# sboardnew.net
KiCad netlist of a schematic drawn in EAGLE
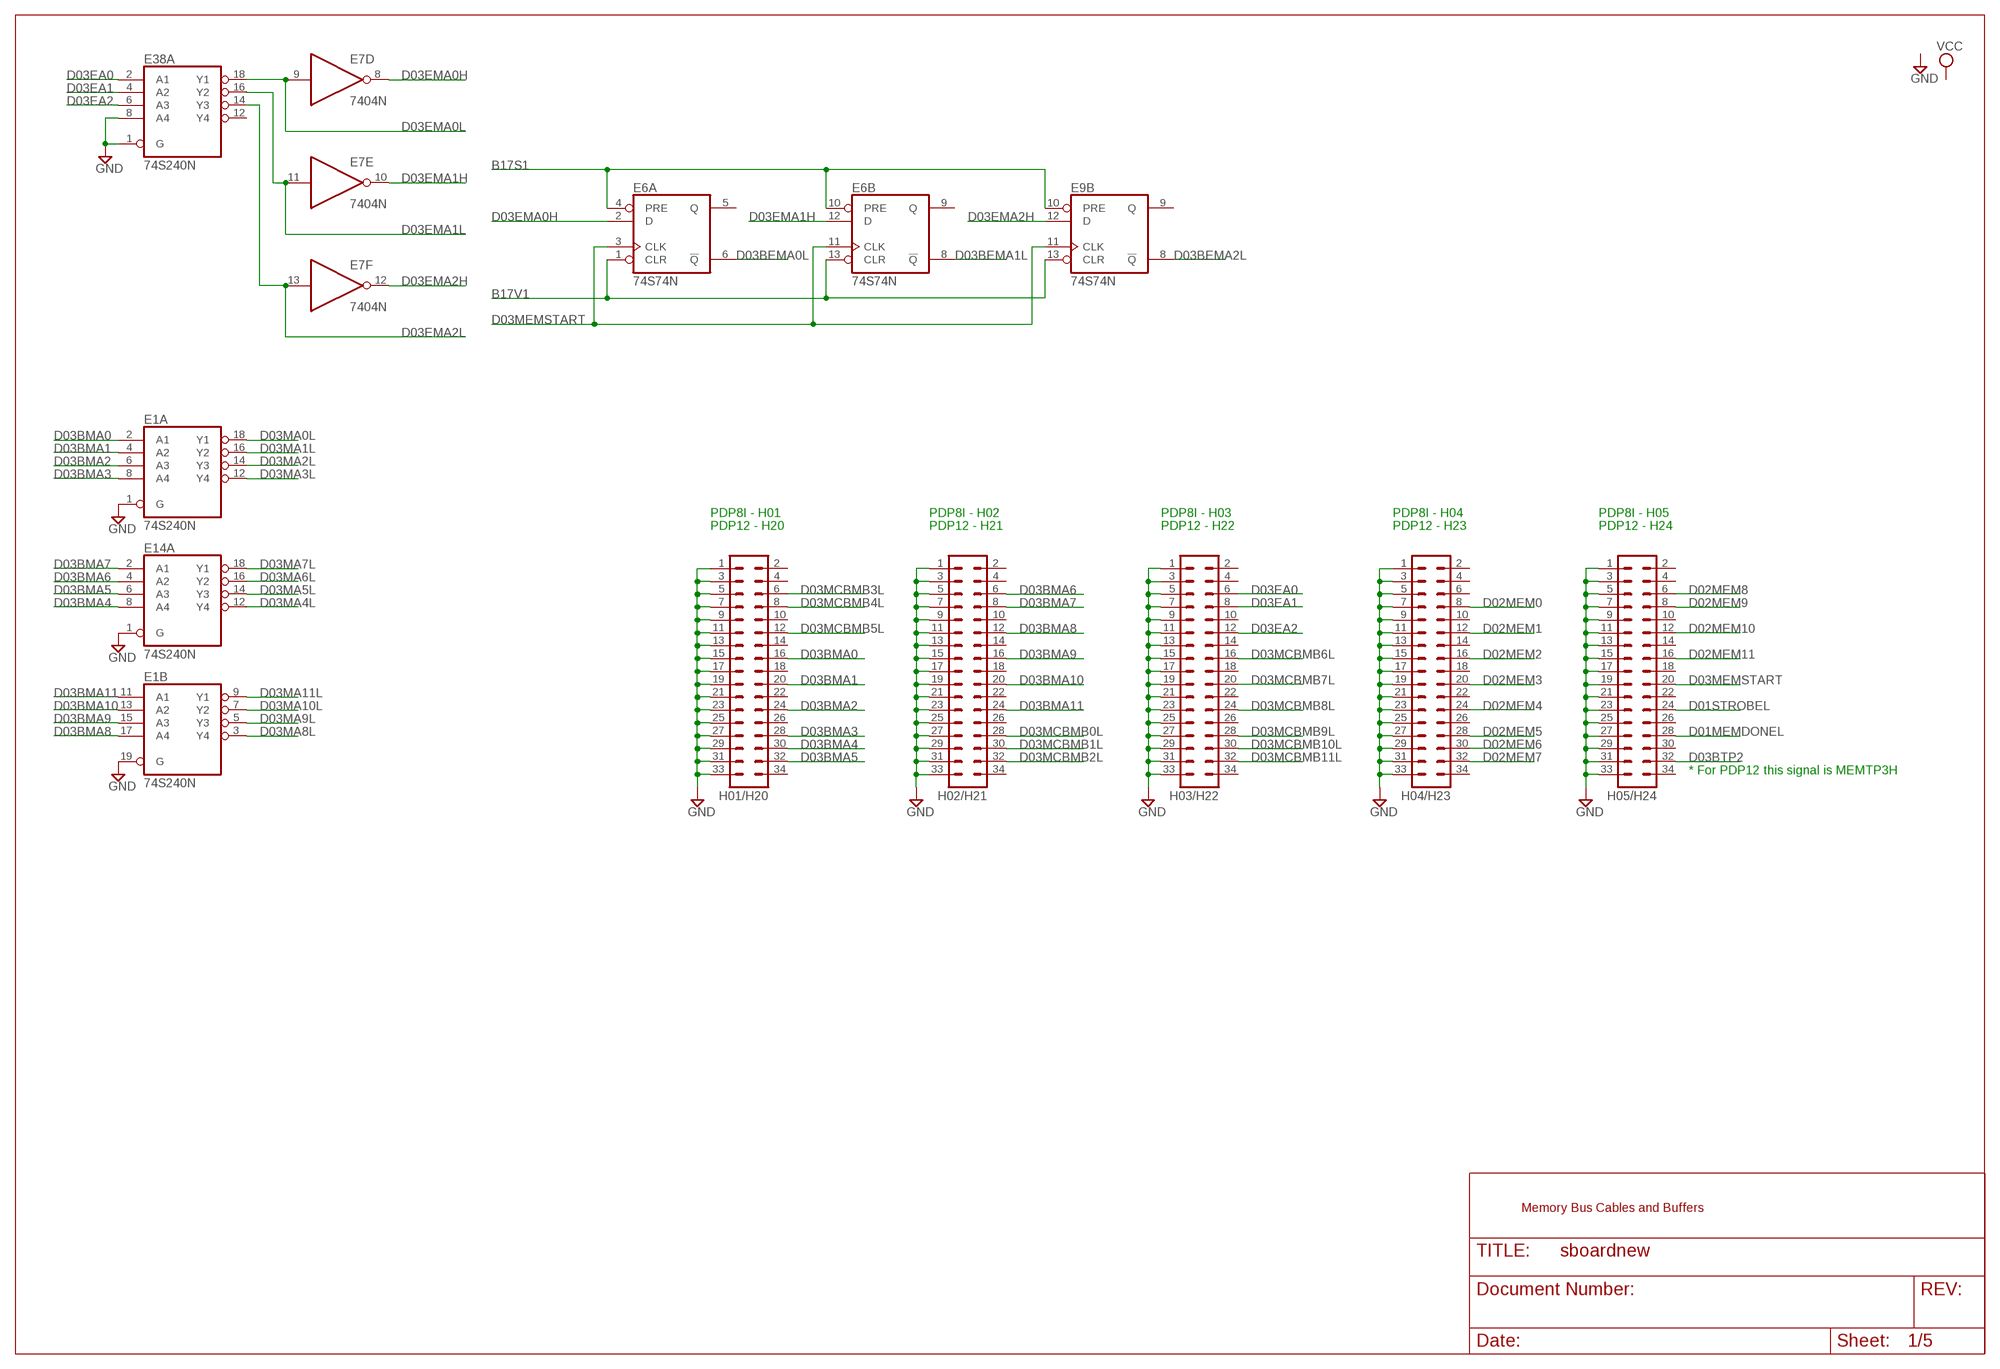
[diagram p0: schematic, sheet 1]
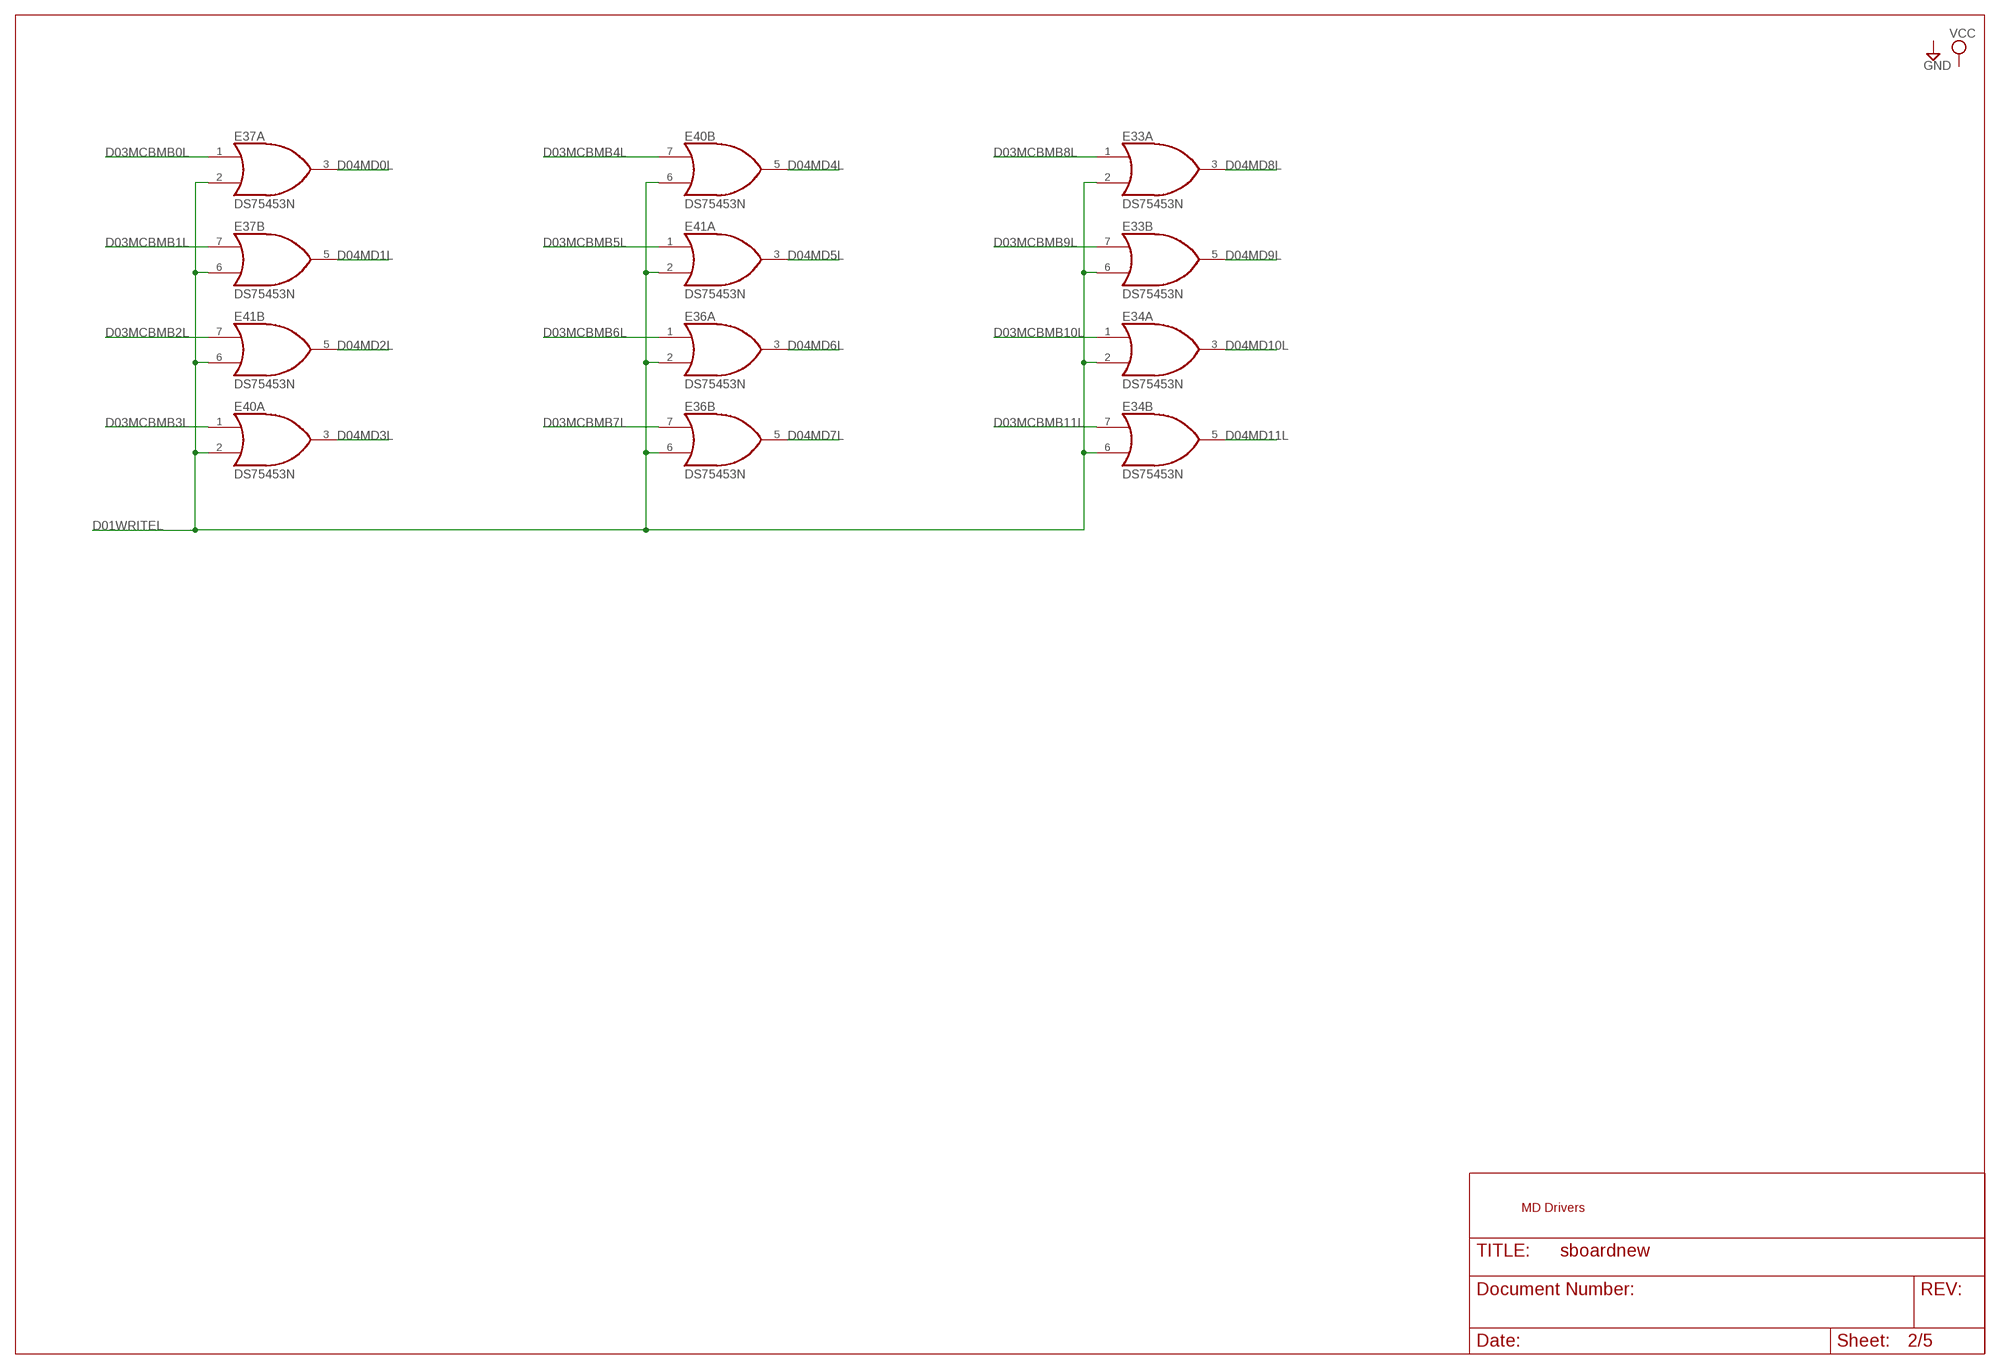
[diagram p1: schematic, sheet 2]
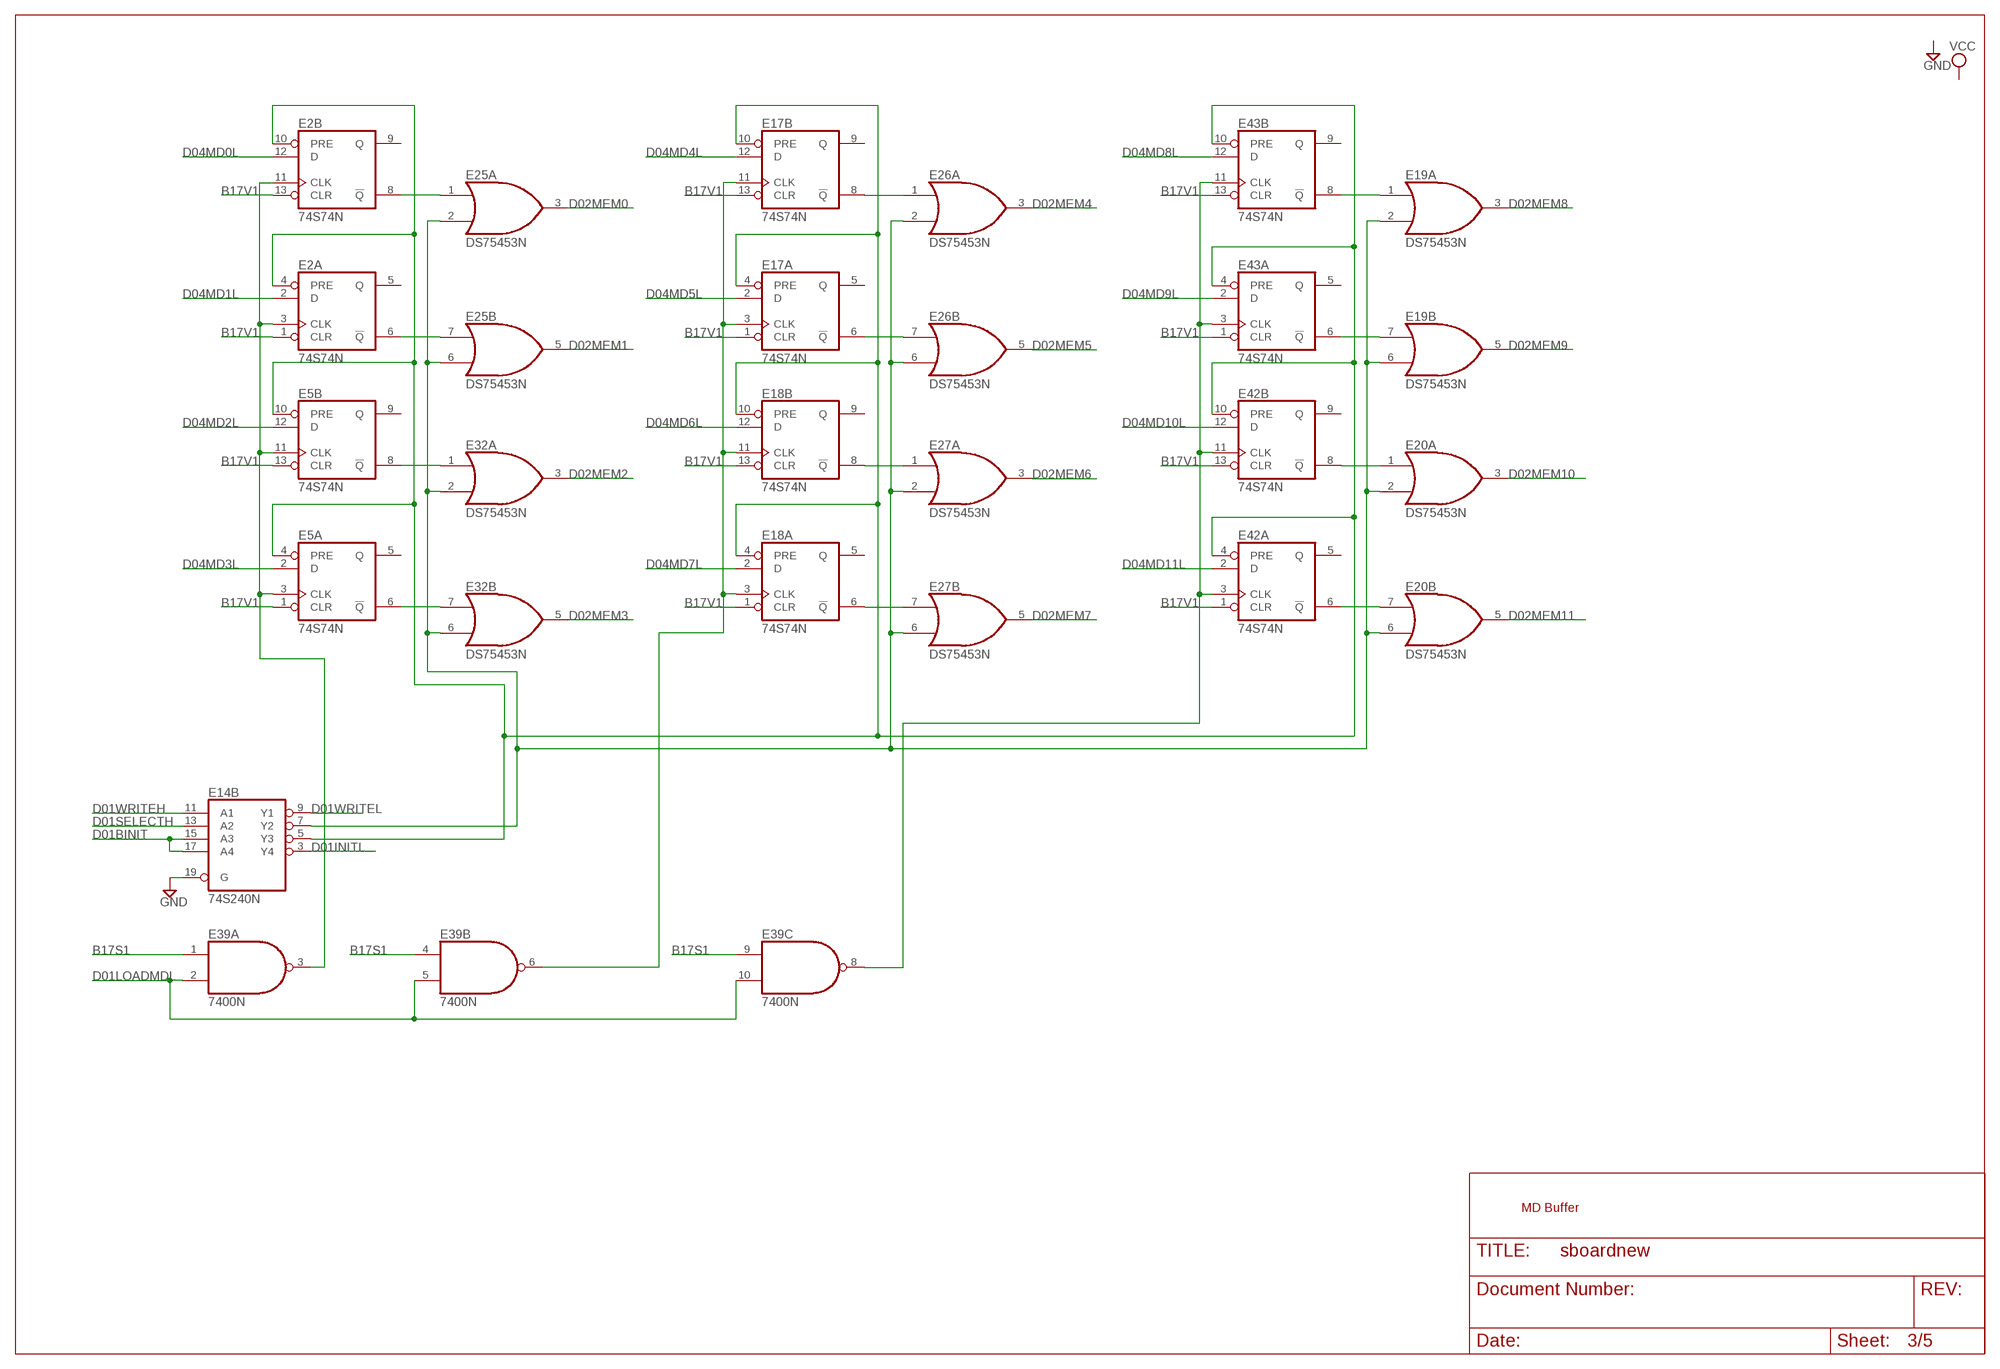
[diagram p2: schematic, sheet 3]
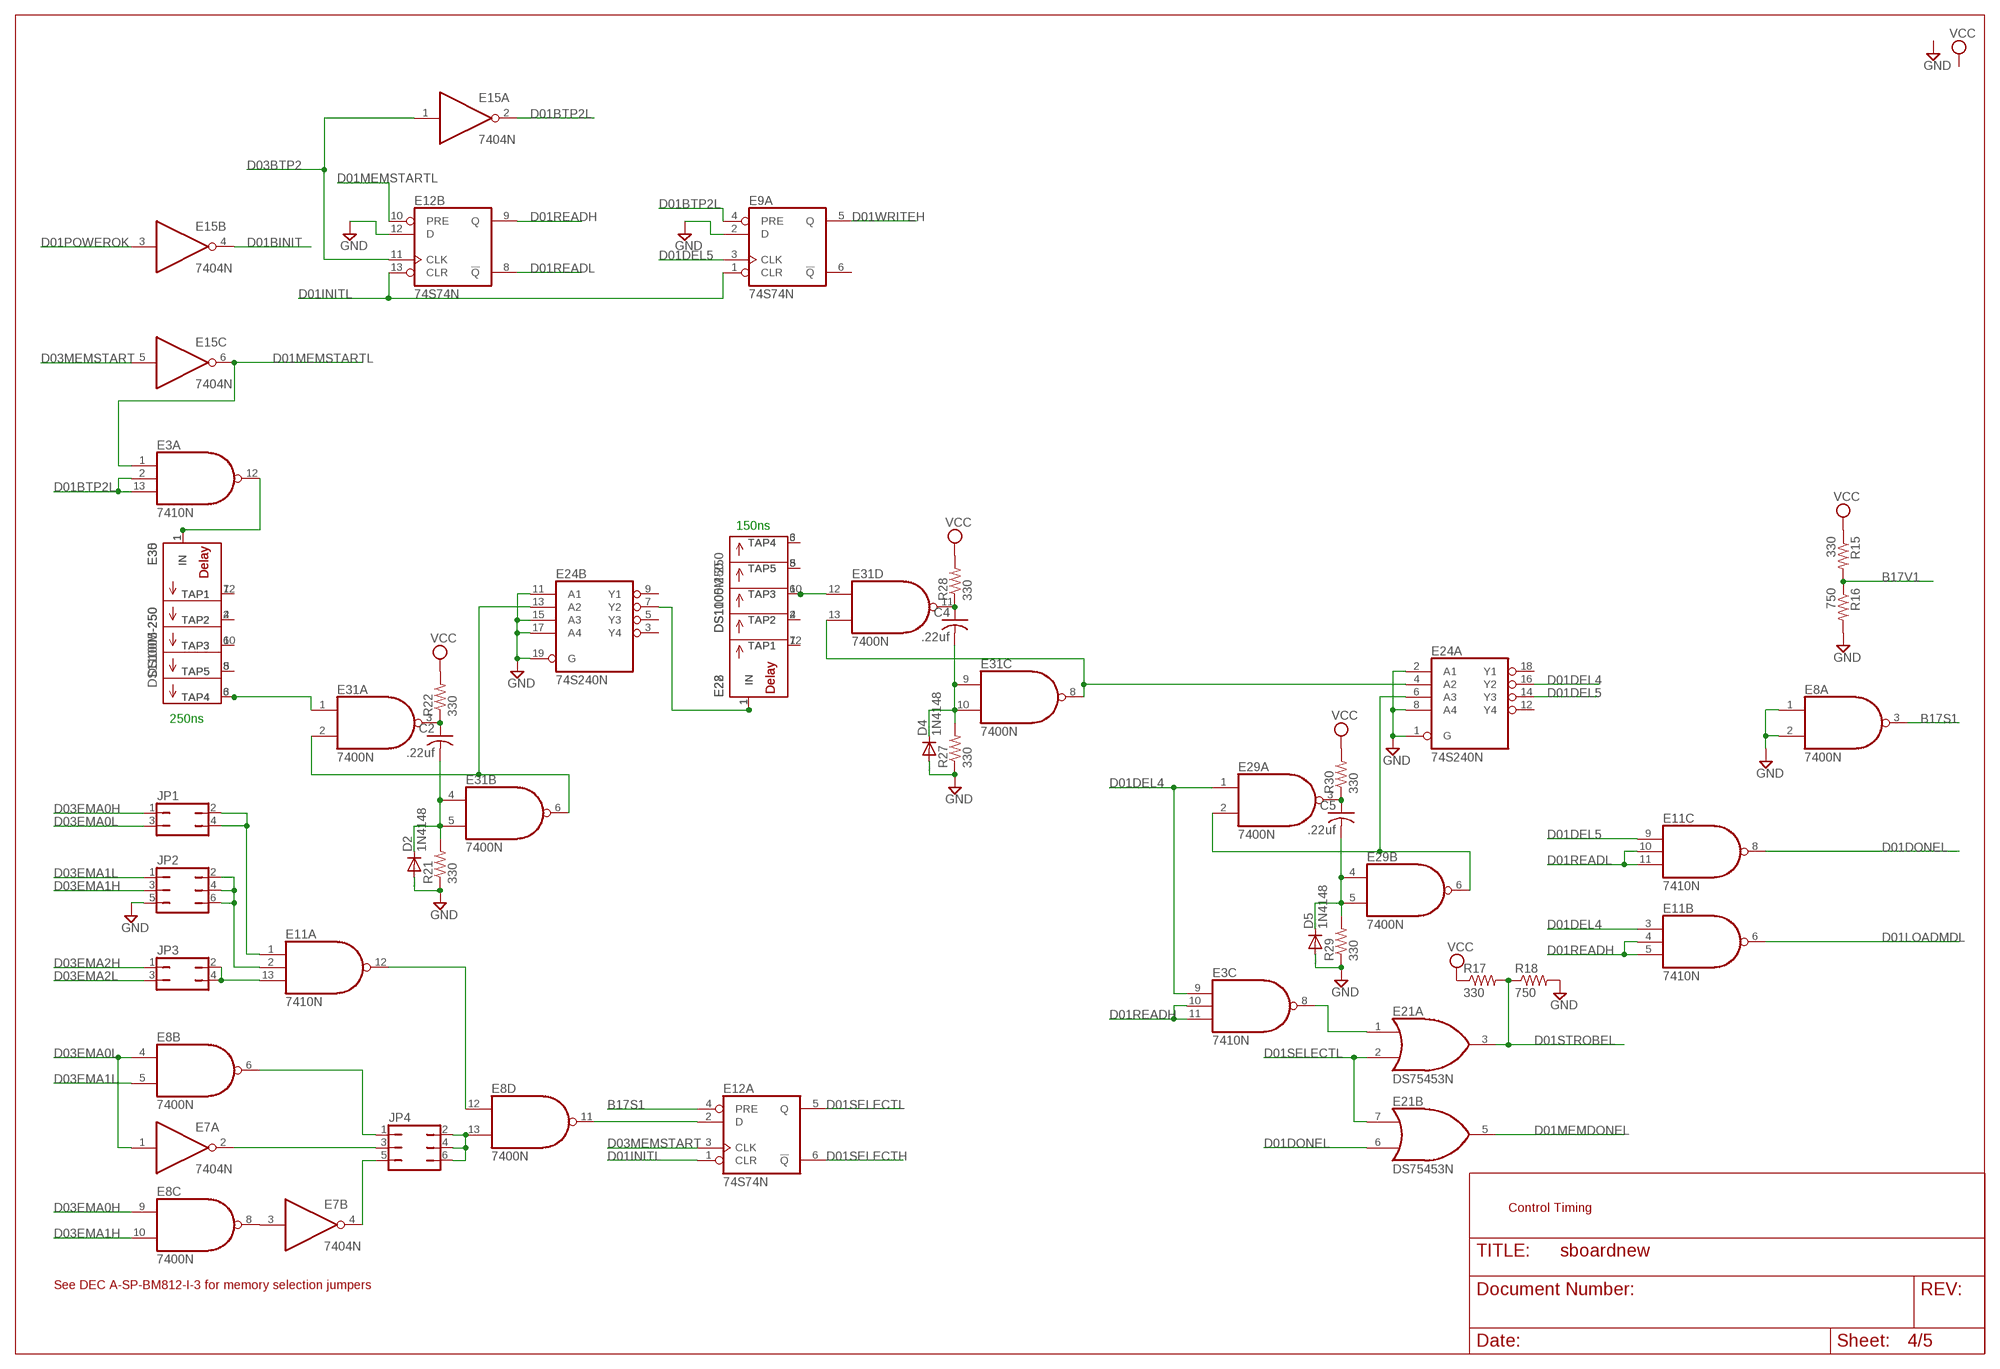
[diagram p3: schematic, sheet 4]
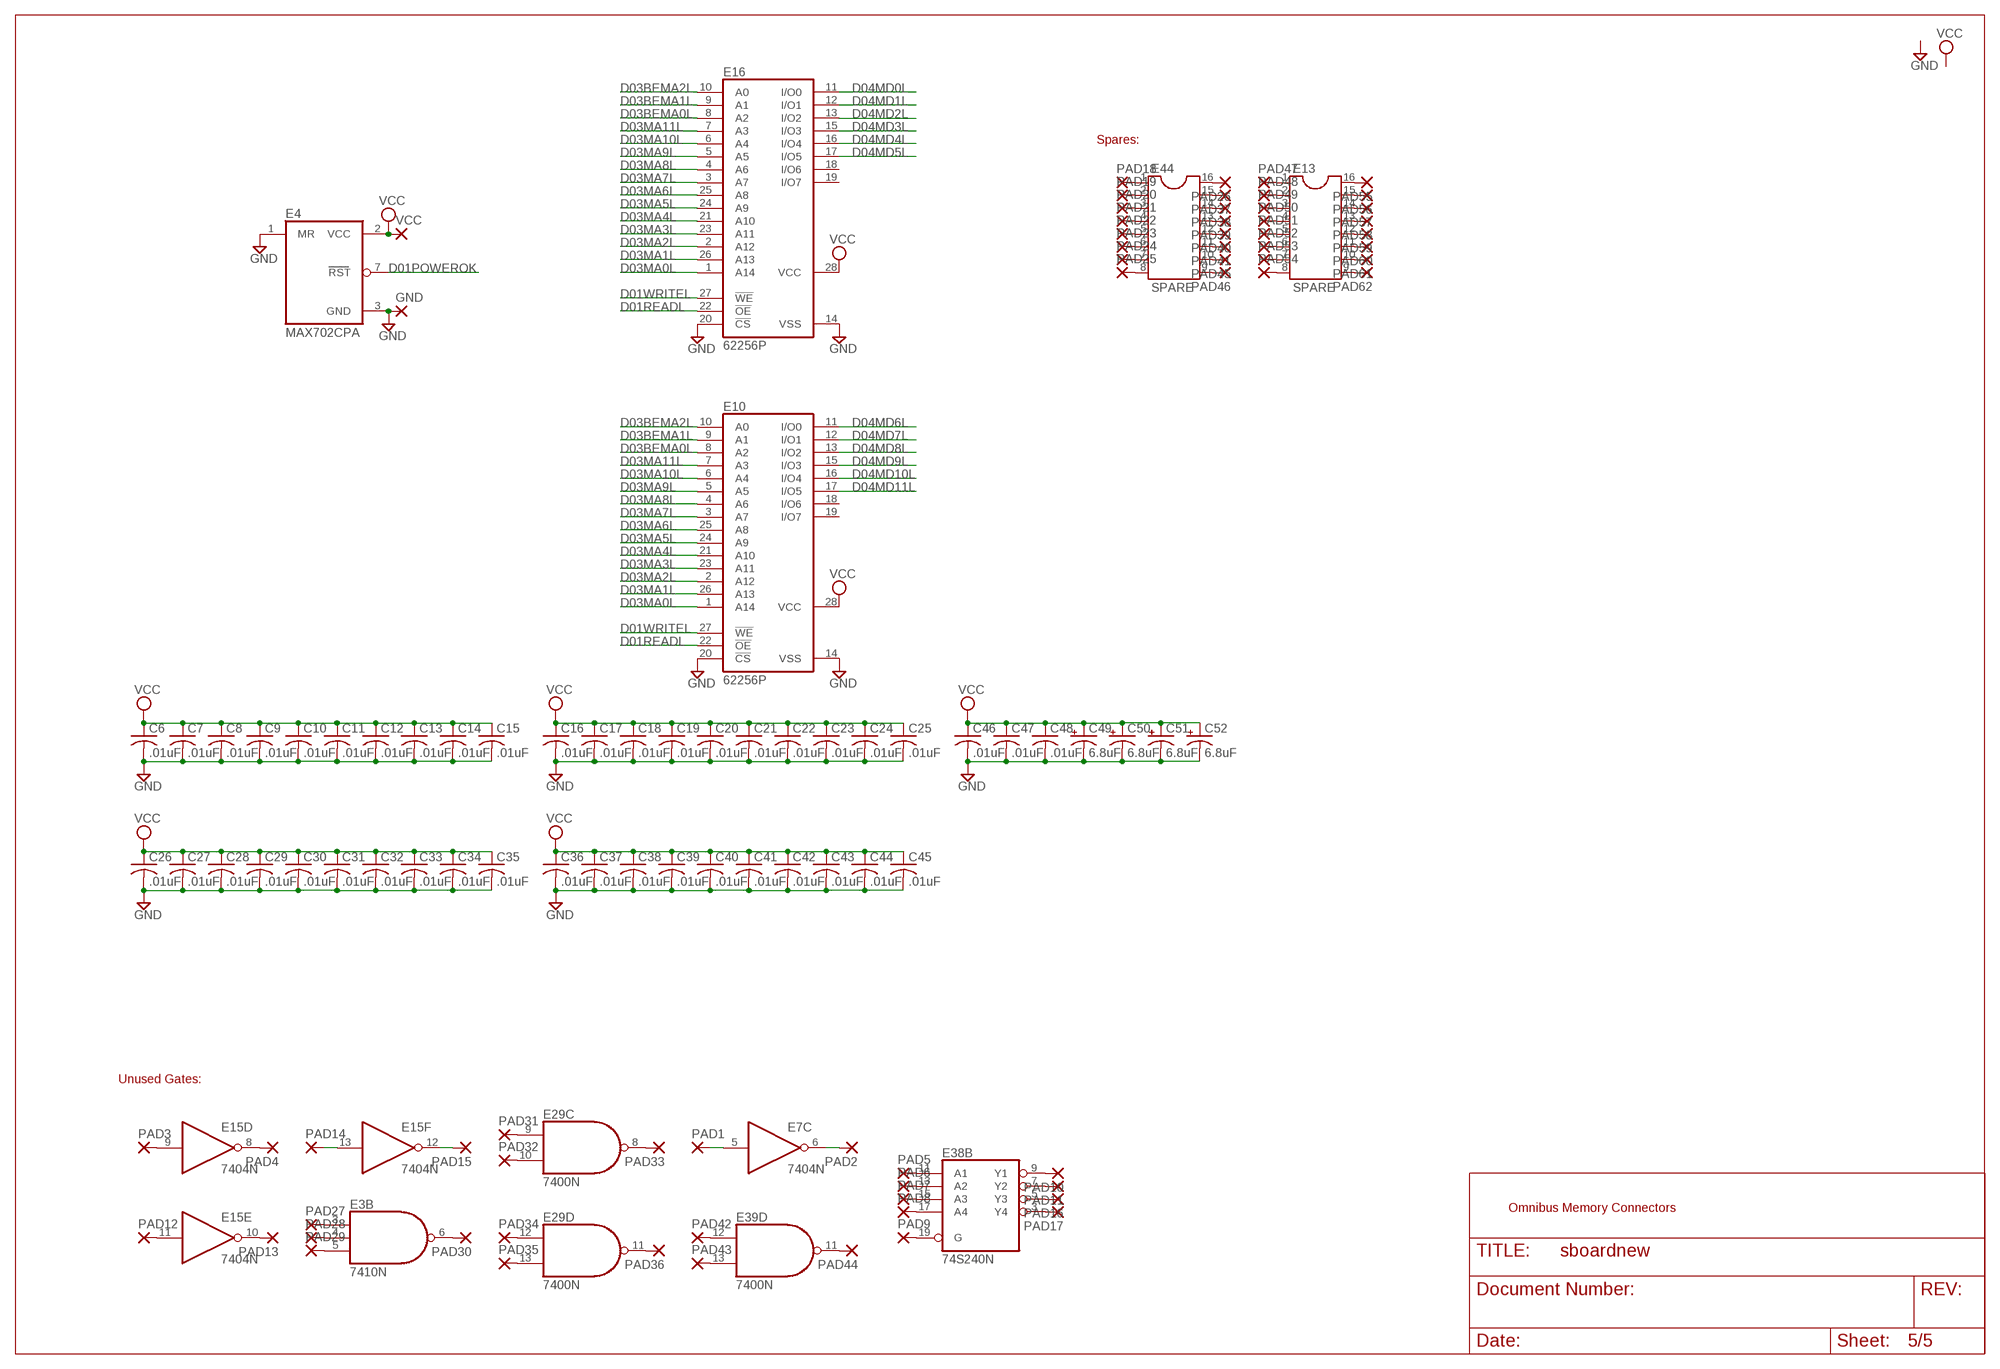
[diagram p4: schematic, sheet 5]

(export (version "E")
  (design (tool "Eeschema 10.0.6"))
  (components
    (comp (ref "E2")
      (value "74S74N")
      (footprint "eagle-import:DIL14")
      (libsource (lib "eagle-import") (part "7474NS"))
    )
    (comp (ref "E5")
      (value "74S74N")
      (footprint "eagle-import:DIL14")
      (libsource (lib "eagle-import") (part "7474NS"))
    )
    (comp (ref "E14")
      (value "74S240N")
      (footprint "eagle-import:DIL20")
      (libsource (lib "eagle-import") (part "74240NS"))
    )
    (comp (ref "E17")
      (value "74S74N")
      (footprint "eagle-import:DIL14")
      (libsource (lib "eagle-import") (part "7474NS"))
    )
    (comp (ref "E18")
      (value "74S74N")
      (footprint "eagle-import:DIL14")
      (libsource (lib "eagle-import") (part "7474NS"))
    )
    (comp (ref "E19")
      (value "DS75453N")
      (footprint "eagle-import:DIL08")
      (libsource (lib "eagle-import") (part "DS75453N"))
    )
    (comp (ref "E20")
      (value "DS75453N")
      (footprint "eagle-import:DIL08")
      (libsource (lib "eagle-import") (part "DS75453N"))
    )
    (comp (ref "E25")
      (value "DS75453N")
      (footprint "eagle-import:DIL08")
      (libsource (lib "eagle-import") (part "DS75453N"))
    )
    (comp (ref "E26")
      (value "DS75453N")
      (footprint "eagle-import:DIL08")
      (libsource (lib "eagle-import") (part "DS75453N"))
    )
    (comp (ref "E27")
      (value "DS75453N")
      (footprint "eagle-import:DIL08")
      (libsource (lib "eagle-import") (part "DS75453N"))
    )
    (comp (ref "E32")
      (value "DS75453N")
      (footprint "eagle-import:DIL08")
      (libsource (lib "eagle-import") (part "DS75453N"))
    )
    (comp (ref "E39")
      (value "7400N")
      (footprint "eagle-import:DIL14")
      (libsource (lib "eagle-import") (part "7400N"))
    )
    (comp (ref "E42")
      (value "74S74N")
      (footprint "eagle-import:DIL14")
      (libsource (lib "eagle-import") (part "7474NS"))
    )
    (comp (ref "E43")
      (value "74S74N")
      (footprint "eagle-import:DIL14")
      (libsource (lib "eagle-import") (part "7474NS"))
    )
    (comp (ref "C6")
      (value ".01uF")
      (footprint "eagle-import:C050-025X075")
      (libsource (lib "eagle-import") (part "C-US050-025X075"))
    )
    (comp (ref "C7")
      (value ".01uF")
      (footprint "eagle-import:C050-025X075")
      (libsource (lib "eagle-import") (part "C-US050-025X075"))
    )
    (comp (ref "C8")
      (value ".01uF")
      (footprint "eagle-import:C050-025X075")
      (libsource (lib "eagle-import") (part "C-US050-025X075"))
    )
    (comp (ref "C9")
      (value ".01uF")
      (footprint "eagle-import:C050-025X075")
      (libsource (lib "eagle-import") (part "C-US050-025X075"))
    )
    (comp (ref "C10")
      (value ".01uF")
      (footprint "eagle-import:C050-025X075")
      (libsource (lib "eagle-import") (part "C-US050-025X075"))
    )
    (comp (ref "C11")
      (value ".01uF")
      (footprint "eagle-import:C050-025X075")
      (libsource (lib "eagle-import") (part "C-US050-025X075"))
    )
    (comp (ref "C12")
      (value ".01uF")
      (footprint "eagle-import:C050-025X075")
      (libsource (lib "eagle-import") (part "C-US050-025X075"))
    )
    (comp (ref "C13")
      (value ".01uF")
      (footprint "eagle-import:C050-025X075")
      (libsource (lib "eagle-import") (part "C-US050-025X075"))
    )
    (comp (ref "C14")
      (value ".01uF")
      (footprint "eagle-import:C050-025X075")
      (libsource (lib "eagle-import") (part "C-US050-025X075"))
    )
    (comp (ref "C15")
      (value ".01uF")
      (footprint "eagle-import:C050-025X075")
      (libsource (lib "eagle-import") (part "C-US050-025X075"))
    )
    (comp (ref "C16")
      (value ".01uF")
      (footprint "eagle-import:C050-025X075")
      (libsource (lib "eagle-import") (part "C-US050-025X075"))
    )
    (comp (ref "C17")
      (value ".01uF")
      (footprint "eagle-import:C050-025X075")
      (libsource (lib "eagle-import") (part "C-US050-025X075"))
    )
    (comp (ref "C18")
      (value ".01uF")
      (footprint "eagle-import:C050-025X075")
      (libsource (lib "eagle-import") (part "C-US050-025X075"))
    )
    (comp (ref "C19")
      (value ".01uF")
      (footprint "eagle-import:C050-025X075")
      (libsource (lib "eagle-import") (part "C-US050-025X075"))
    )
    (comp (ref "C20")
      (value ".01uF")
      (footprint "eagle-import:C050-025X075")
      (libsource (lib "eagle-import") (part "C-US050-025X075"))
    )
    (comp (ref "C21")
      (value ".01uF")
      (footprint "eagle-import:C050-025X075")
      (libsource (lib "eagle-import") (part "C-US050-025X075"))
    )
    (comp (ref "C22")
      (value ".01uF")
      (footprint "eagle-import:C050-025X075")
      (libsource (lib "eagle-import") (part "C-US050-025X075"))
    )
    (comp (ref "C23")
      (value ".01uF")
      (footprint "eagle-import:C050-025X075")
      (libsource (lib "eagle-import") (part "C-US050-025X075"))
    )
    (comp (ref "C24")
      (value ".01uF")
      (footprint "eagle-import:C050-025X075")
      (libsource (lib "eagle-import") (part "C-US050-025X075"))
    )
    (comp (ref "C25")
      (value ".01uF")
      (footprint "eagle-import:C050-025X075")
      (libsource (lib "eagle-import") (part "C-US050-025X075"))
    )
    (comp (ref "C26")
      (value ".01uF")
      (footprint "eagle-import:C050-025X075")
      (libsource (lib "eagle-import") (part "C-US050-025X075"))
    )
    (comp (ref "C27")
      (value ".01uF")
      (footprint "eagle-import:C050-025X075")
      (libsource (lib "eagle-import") (part "C-US050-025X075"))
    )
    (comp (ref "C28")
      (value ".01uF")
      (footprint "eagle-import:C050-025X075")
      (libsource (lib "eagle-import") (part "C-US050-025X075"))
    )
    (comp (ref "C29")
      (value ".01uF")
      (footprint "eagle-import:C050-025X075")
      (libsource (lib "eagle-import") (part "C-US050-025X075"))
    )
    (comp (ref "C30")
      (value ".01uF")
      (footprint "eagle-import:C050-025X075")
      (libsource (lib "eagle-import") (part "C-US050-025X075"))
    )
    (comp (ref "C31")
      (value ".01uF")
      (footprint "eagle-import:C050-025X075")
      (libsource (lib "eagle-import") (part "C-US050-025X075"))
    )
    (comp (ref "C32")
      (value ".01uF")
      (footprint "eagle-import:C050-025X075")
      (libsource (lib "eagle-import") (part "C-US050-025X075"))
    )
    (comp (ref "C33")
      (value ".01uF")
      (footprint "eagle-import:C050-025X075")
      (libsource (lib "eagle-import") (part "C-US050-025X075"))
    )
    (comp (ref "C34")
      (value ".01uF")
      (footprint "eagle-import:C050-025X075")
      (libsource (lib "eagle-import") (part "C-US050-025X075"))
    )
    (comp (ref "C35")
      (value ".01uF")
      (footprint "eagle-import:C050-025X075")
      (libsource (lib "eagle-import") (part "C-US050-025X075"))
    )
    (comp (ref "C36")
      (value ".01uF")
      (footprint "eagle-import:C050-025X075")
      (libsource (lib "eagle-import") (part "C-US050-025X075"))
    )
    (comp (ref "C37")
      (value ".01uF")
      (footprint "eagle-import:C050-025X075")
      (libsource (lib "eagle-import") (part "C-US050-025X075"))
    )
    (comp (ref "C38")
      (value ".01uF")
      (footprint "eagle-import:C050-025X075")
      (libsource (lib "eagle-import") (part "C-US050-025X075"))
    )
    (comp (ref "C39")
      (value ".01uF")
      (footprint "eagle-import:C050-025X075")
      (libsource (lib "eagle-import") (part "C-US050-025X075"))
    )
    (comp (ref "C40")
      (value ".01uF")
      (footprint "eagle-import:C050-025X075")
      (libsource (lib "eagle-import") (part "C-US050-025X075"))
    )
    (comp (ref "C41")
      (value ".01uF")
      (footprint "eagle-import:C050-025X075")
      (libsource (lib "eagle-import") (part "C-US050-025X075"))
    )
    (comp (ref "C42")
      (value ".01uF")
      (footprint "eagle-import:C050-025X075")
      (libsource (lib "eagle-import") (part "C-US050-025X075"))
    )
    (comp (ref "C43")
      (value ".01uF")
      (footprint "eagle-import:C050-025X075")
      (libsource (lib "eagle-import") (part "C-US050-025X075"))
    )
    (comp (ref "C44")
      (value ".01uF")
      (footprint "eagle-import:C050-025X075")
      (libsource (lib "eagle-import") (part "C-US050-025X075"))
    )
    (comp (ref "C45")
      (value ".01uF")
      (footprint "eagle-import:C050-025X075")
      (libsource (lib "eagle-import") (part "C-US050-025X075"))
    )
    (comp (ref "C46")
      (value ".01uF")
      (footprint "eagle-import:C050-025X075")
      (libsource (lib "eagle-import") (part "C-US050-025X075"))
    )
    (comp (ref "C47")
      (value ".01uF")
      (footprint "eagle-import:C050-025X075")
      (libsource (lib "eagle-import") (part "C-US050-025X075"))
    )
    (comp (ref "C48")
      (value ".01uF")
      (footprint "eagle-import:C050-025X075")
      (libsource (lib "eagle-import") (part "C-US050-025X075"))
    )
    (comp (ref "C49")
      (value "6.8uF")
      (footprint "eagle-import:E22-6")
      (libsource (lib "eagle-import") (part "CPOL-USE22-6AXIAL"))
    )
    (comp (ref "C50")
      (value "6.8uF")
      (footprint "eagle-import:E22-6")
      (libsource (lib "eagle-import") (part "CPOL-USE22-6AXIAL"))
    )
    (comp (ref "C51")
      (value "6.8uF")
      (footprint "eagle-import:E22-6")
      (libsource (lib "eagle-import") (part "CPOL-USE22-6AXIAL"))
    )
    (comp (ref "C52")
      (value "6.8uF")
      (footprint "eagle-import:E22-6")
      (libsource (lib "eagle-import") (part "CPOL-USE22-6AXIAL"))
    )
    (comp (ref "E3")
      (value "7410N")
      (footprint "eagle-import:DIL14")
      (libsource (lib "eagle-import") (part "7410N"))
    )
    (comp (ref "E4")
      (value "MAX702CPA")
      (footprint "eagle-import:DIL08")
      (fields (field (name "MF") "MAXIM") (field (name "MPN") "MAX702CPA+"))
      (libsource (lib "eagle-import") (part "MAX702CPA"))
    )
    (comp (ref "E7")
      (value "7404N")
      (footprint "eagle-import:DIL14")
      (libsource (lib "eagle-import") (part "7404N"))
    )
    (comp (ref "E10")
      (value "62256P")
      (footprint "eagle-import:DIL28-6")
      (libsource (lib "eagle-import") (part "62256P"))
    )
    (comp (ref "E13")
      (value "SPARE")
      (footprint "eagle-import:DIL16")
      (libsource (lib "eagle-import") (part "DIL16"))
    )
    (comp (ref "E15")
      (value "7404N")
      (footprint "eagle-import:DIL14")
      (libsource (lib "eagle-import") (part "7404N"))
    )
    (comp (ref "E16")
      (value "62256P")
      (footprint "eagle-import:DIL28-6")
      (libsource (lib "eagle-import") (part "62256P"))
    )
    (comp (ref "E29")
      (value "7400N")
      (footprint "eagle-import:DIL14")
      (libsource (lib "eagle-import") (part "7400N"))
    )
    (comp (ref "E38")
      (value "74S240N")
      (footprint "eagle-import:DIL20")
      (libsource (lib "eagle-import") (part "74240NS"))
    )
    (comp (ref "E44")
      (value "SPARE")
      (footprint "eagle-import:DIL16")
      (libsource (lib "eagle-import") (part "DIL16"))
    )
    (comp (ref "GND")
      (value "2,15/1,0")
      (footprint "eagle-import:2,15_1,0")
      (libsource (lib "eagle-import") (part "2,15/1,0"))
    )
    (comp (ref "PAD1")
      (value "1,6/0,8")
      (footprint "eagle-import:1,6_0,8")
      (libsource (lib "eagle-import") (part "1,6/0,8"))
    )
    (comp (ref "PAD2")
      (value "1,6/0,8")
      (footprint "eagle-import:1,6_0,8")
      (libsource (lib "eagle-import") (part "1,6/0,8"))
    )
    (comp (ref "PAD3")
      (value "1,6/0,8")
      (footprint "eagle-import:1,6_0,8")
      (libsource (lib "eagle-import") (part "1,6/0,8"))
    )
    (comp (ref "PAD4")
      (value "1,6/0,8")
      (footprint "eagle-import:1,6_0,8")
      (libsource (lib "eagle-import") (part "1,6/0,8"))
    )
    (comp (ref "PAD5")
      (value "1,6/0,8")
      (footprint "eagle-import:1,6_0,8")
      (libsource (lib "eagle-import") (part "1,6/0,8"))
    )
    (comp (ref "PAD6")
      (value "1,6/0,8")
      (footprint "eagle-import:1,6_0,8")
      (libsource (lib "eagle-import") (part "1,6/0,8"))
    )
    (comp (ref "PAD7")
      (value "1,6/0,8")
      (footprint "eagle-import:1,6_0,8")
      (libsource (lib "eagle-import") (part "1,6/0,8"))
    )
    (comp (ref "PAD8")
      (value "1,6/0,8")
      (footprint "eagle-import:1,6_0,8")
      (libsource (lib "eagle-import") (part "1,6/0,8"))
    )
    (comp (ref "PAD9")
      (value "1,6/0,8")
      (footprint "eagle-import:1,6_0,8")
      (libsource (lib "eagle-import") (part "1,6/0,8"))
    )
    (comp (ref "PAD10")
      (value "1,6/0,8")
      (footprint "eagle-import:1,6_0,8")
      (libsource (lib "eagle-import") (part "1,6/0,8"))
    )
    (comp (ref "PAD11")
      (value "1,6/0,8")
      (footprint "eagle-import:1,6_0,8")
      (libsource (lib "eagle-import") (part "1,6/0,8"))
    )
    (comp (ref "PAD12")
      (value "1,6/0,8")
      (footprint "eagle-import:1,6_0,8")
      (libsource (lib "eagle-import") (part "1,6/0,8"))
    )
    (comp (ref "PAD13")
      (value "1,6/0,8")
      (footprint "eagle-import:1,6_0,8")
      (libsource (lib "eagle-import") (part "1,6/0,8"))
    )
    (comp (ref "PAD14")
      (value "1,6/0,8")
      (footprint "eagle-import:1,6_0,8")
      (libsource (lib "eagle-import") (part "1,6/0,8"))
    )
    (comp (ref "PAD15")
      (value "1,6/0,8")
      (footprint "eagle-import:1,6_0,8")
      (libsource (lib "eagle-import") (part "1,6/0,8"))
    )
    (comp (ref "PAD16")
      (value "1,6/0,8")
      (footprint "eagle-import:1,6_0,8")
      (libsource (lib "eagle-import") (part "1,6/0,8"))
    )
    (comp (ref "PAD17")
      (value "1,6/0,8")
      (footprint "eagle-import:1,6_0,8")
      (libsource (lib "eagle-import") (part "1,6/0,8"))
    )
    (comp (ref "PAD18")
      (value "1,6/0,8")
      (footprint "eagle-import:1,6_0,8")
      (libsource (lib "eagle-import") (part "1,6/0,8"))
    )
    (comp (ref "PAD19")
      (value "1,6/0,8")
      (footprint "eagle-import:1,6_0,8")
      (libsource (lib "eagle-import") (part "1,6/0,8"))
    )
    (comp (ref "PAD20")
      (value "1,6/0,8")
      (footprint "eagle-import:1,6_0,8")
      (libsource (lib "eagle-import") (part "1,6/0,8"))
    )
    (comp (ref "PAD21")
      (value "1,6/0,8")
      (footprint "eagle-import:1,6_0,8")
      (libsource (lib "eagle-import") (part "1,6/0,8"))
    )
    (comp (ref "PAD22")
      (value "1,6/0,8")
      (footprint "eagle-import:1,6_0,8")
      (libsource (lib "eagle-import") (part "1,6/0,8"))
    )
    (comp (ref "PAD23")
      (value "1,6/0,8")
      (footprint "eagle-import:1,6_0,8")
      (libsource (lib "eagle-import") (part "1,6/0,8"))
    )
    (comp (ref "PAD24")
      (value "1,6/0,8")
      (footprint "eagle-import:1,6_0,8")
      (libsource (lib "eagle-import") (part "1,6/0,8"))
    )
    (comp (ref "PAD25")
      (value "1,6/0,8")
      (footprint "eagle-import:1,6_0,8")
      (libsource (lib "eagle-import") (part "1,6/0,8"))
    )
    (comp (ref "PAD26")
      (value "1,6/0,8")
      (footprint "eagle-import:1,6_0,8")
      (libsource (lib "eagle-import") (part "1,6/0,8"))
    )
    (comp (ref "PAD27")
      (value "1,6/0,8")
      (footprint "eagle-import:1,6_0,8")
      (libsource (lib "eagle-import") (part "1,6/0,8"))
    )
    (comp (ref "PAD28")
      (value "1,6/0,8")
      (footprint "eagle-import:1,6_0,8")
      (libsource (lib "eagle-import") (part "1,6/0,8"))
    )
    (comp (ref "PAD29")
      (value "1,6/0,8")
      (footprint "eagle-import:1,6_0,8")
      (libsource (lib "eagle-import") (part "1,6/0,8"))
    )
    (comp (ref "PAD30")
      (value "1,6/0,8")
      (footprint "eagle-import:1,6_0,8")
      (libsource (lib "eagle-import") (part "1,6/0,8"))
    )
    (comp (ref "PAD31")
      (value "1,6/0,8")
      (footprint "eagle-import:1,6_0,8")
      (libsource (lib "eagle-import") (part "1,6/0,8"))
    )
    (comp (ref "PAD32")
      (value "1,6/0,8")
      (footprint "eagle-import:1,6_0,8")
      (libsource (lib "eagle-import") (part "1,6/0,8"))
    )
    (comp (ref "PAD33")
      (value "1,6/0,8")
      (footprint "eagle-import:1,6_0,8")
      (libsource (lib "eagle-import") (part "1,6/0,8"))
    )
    (comp (ref "PAD34")
      (value "1,6/0,8")
      (footprint "eagle-import:1,6_0,8")
      (libsource (lib "eagle-import") (part "1,6/0,8"))
    )
    (comp (ref "PAD35")
      (value "1,6/0,8")
      (footprint "eagle-import:1,6_0,8")
      (libsource (lib "eagle-import") (part "1,6/0,8"))
    )
    (comp (ref "PAD36")
      (value "1,6/0,8")
      (footprint "eagle-import:1,6_0,8")
      (libsource (lib "eagle-import") (part "1,6/0,8"))
    )
    (comp (ref "PAD37")
      (value "1,6/0,8")
      (footprint "eagle-import:1,6_0,8")
      (libsource (lib "eagle-import") (part "1,6/0,8"))
    )
    (comp (ref "PAD38")
      (value "1,6/0,8")
      (footprint "eagle-import:1,6_0,8")
      (libsource (lib "eagle-import") (part "1,6/0,8"))
    )
    (comp (ref "PAD39")
      (value "1,6/0,8")
      (footprint "eagle-import:1,6_0,8")
      (libsource (lib "eagle-import") (part "1,6/0,8"))
    )
    (comp (ref "PAD40")
      (value "1,6/0,8")
      (footprint "eagle-import:1,6_0,8")
      (libsource (lib "eagle-import") (part "1,6/0,8"))
    )
    (comp (ref "PAD41")
      (value "1,6/0,8")
      (footprint "eagle-import:1,6_0,8")
      (libsource (lib "eagle-import") (part "1,6/0,8"))
    )
    (comp (ref "PAD42")
      (value "1,6/0,8")
      (footprint "eagle-import:1,6_0,8")
      (libsource (lib "eagle-import") (part "1,6/0,8"))
    )
    (comp (ref "PAD43")
      (value "1,6/0,8")
      (footprint "eagle-import:1,6_0,8")
      (libsource (lib "eagle-import") (part "1,6/0,8"))
    )
    (comp (ref "PAD44")
      (value "1,6/0,8")
      (footprint "eagle-import:1,6_0,8")
      (libsource (lib "eagle-import") (part "1,6/0,8"))
    )
    (comp (ref "PAD45")
      (value "1,6/0,8")
      (footprint "eagle-import:1,6_0,8")
      (libsource (lib "eagle-import") (part "1,6/0,8"))
    )
    (comp (ref "PAD46")
      (value "1,6/0,8")
      (footprint "eagle-import:1,6_0,8")
      (libsource (lib "eagle-import") (part "1,6/0,8"))
    )
    (comp (ref "PAD47")
      (value "1,6/0,8")
      (footprint "eagle-import:1,6_0,8")
      (libsource (lib "eagle-import") (part "1,6/0,8"))
    )
    (comp (ref "PAD48")
      (value "1,6/0,8")
      (footprint "eagle-import:1,6_0,8")
      (libsource (lib "eagle-import") (part "1,6/0,8"))
    )
    (comp (ref "PAD49")
      (value "1,6/0,8")
      (footprint "eagle-import:1,6_0,8")
      (libsource (lib "eagle-import") (part "1,6/0,8"))
    )
    (comp (ref "PAD50")
      (value "1,6/0,8")
      (footprint "eagle-import:1,6_0,8")
      (libsource (lib "eagle-import") (part "1,6/0,8"))
    )
    (comp (ref "PAD51")
      (value "1,6/0,8")
      (footprint "eagle-import:1,6_0,8")
      (libsource (lib "eagle-import") (part "1,6/0,8"))
    )
    (comp (ref "PAD52")
      (value "1,6/0,8")
      (footprint "eagle-import:1,6_0,8")
      (libsource (lib "eagle-import") (part "1,6/0,8"))
    )
    (comp (ref "PAD53")
      (value "1,6/0,8")
      (footprint "eagle-import:1,6_0,8")
      (libsource (lib "eagle-import") (part "1,6/0,8"))
    )
    (comp (ref "PAD54")
      (value "1,6/0,8")
      (footprint "eagle-import:1,6_0,8")
      (libsource (lib "eagle-import") (part "1,6/0,8"))
    )
    (comp (ref "PAD55")
      (value "1,6/0,8")
      (footprint "eagle-import:1,6_0,8")
      (libsource (lib "eagle-import") (part "1,6/0,8"))
    )
    (comp (ref "PAD56")
      (value "1,6/0,8")
      (footprint "eagle-import:1,6_0,8")
      (libsource (lib "eagle-import") (part "1,6/0,8"))
    )
    (comp (ref "PAD57")
      (value "1,6/0,8")
      (footprint "eagle-import:1,6_0,8")
      (libsource (lib "eagle-import") (part "1,6/0,8"))
    )
    (comp (ref "PAD58")
      (value "1,6/0,8")
      (footprint "eagle-import:1,6_0,8")
      (libsource (lib "eagle-import") (part "1,6/0,8"))
    )
    (comp (ref "PAD59")
      (value "1,6/0,8")
      (footprint "eagle-import:1,6_0,8")
      (libsource (lib "eagle-import") (part "1,6/0,8"))
    )
    (comp (ref "PAD60")
      (value "1,6/0,8")
      (footprint "eagle-import:1,6_0,8")
      (libsource (lib "eagle-import") (part "1,6/0,8"))
    )
    (comp (ref "PAD61")
      (value "1,6/0,8")
      (footprint "eagle-import:1,6_0,8")
      (libsource (lib "eagle-import") (part "1,6/0,8"))
    )
    (comp (ref "PAD62")
      (value "1,6/0,8")
      (footprint "eagle-import:1,6_0,8")
      (libsource (lib "eagle-import") (part "1,6/0,8"))
    )
    (comp (ref "VCC")
      (value "2,15/1,0")
      (footprint "eagle-import:2,15_1,0")
      (libsource (lib "eagle-import") (part "2,15/1,0"))
    )
    (comp (ref "E1")
      (value "74S240N")
      (footprint "eagle-import:DIL20")
      (libsource (lib "eagle-import") (part "74240NS"))
    )
    (comp (ref "E6")
      (value "74S74N")
      (footprint "eagle-import:DIL14")
      (libsource (lib "eagle-import") (part "7474NS"))
    )
    (comp (ref "E9")
      (value "74S74N")
      (footprint "eagle-import:DIL14")
      (libsource (lib "eagle-import") (part "7474NS"))
    )
    (comp (ref "H01/H20")
      (value "MA17-2")
      (footprint "eagle-import:MA17-2")
      (libsource (lib "eagle-import") (part "MA17-2"))
    )
    (comp (ref "H02/H21")
      (value "MA17-2")
      (footprint "eagle-import:MA17-2")
      (libsource (lib "eagle-import") (part "MA17-2"))
    )
    (comp (ref "H03/H22")
      (value "MA17-2")
      (footprint "eagle-import:MA17-2")
      (libsource (lib "eagle-import") (part "MA17-2"))
    )
    (comp (ref "H04/H23")
      (value "MA17-2")
      (footprint "eagle-import:MA17-2")
      (libsource (lib "eagle-import") (part "MA17-2"))
    )
    (comp (ref "H05/H24")
      (value "MA17-2")
      (footprint "eagle-import:MA17-2")
      (libsource (lib "eagle-import") (part "MA17-2"))
    )
    (comp (ref "E33")
      (value "DS75453N")
      (footprint "eagle-import:DIL08")
      (libsource (lib "eagle-import") (part "DS75453N"))
    )
    (comp (ref "E34")
      (value "DS75453N")
      (footprint "eagle-import:DIL08")
      (libsource (lib "eagle-import") (part "DS75453N"))
    )
    (comp (ref "E36")
      (value "DS75453N")
      (footprint "eagle-import:DIL08")
      (libsource (lib "eagle-import") (part "DS75453N"))
    )
    (comp (ref "E37")
      (value "DS75453N")
      (footprint "eagle-import:DIL08")
      (libsource (lib "eagle-import") (part "DS75453N"))
    )
    (comp (ref "E40")
      (value "DS75453N")
      (footprint "eagle-import:DIL08")
      (libsource (lib "eagle-import") (part "DS75453N"))
    )
    (comp (ref "E41")
      (value "DS75453N")
      (footprint "eagle-import:DIL08")
      (libsource (lib "eagle-import") (part "DS75453N"))
    )
    (comp (ref "C2")
      (value ".22uf")
      (footprint "eagle-import:C050-025X075")
      (libsource (lib "eagle-import") (part "C-US050-025X075"))
    )
    (comp (ref "C4")
      (value ".22uf")
      (footprint "eagle-import:C050-025X075")
      (libsource (lib "eagle-import") (part "C-US050-025X075"))
    )
    (comp (ref "C5")
      (value ".22uf")
      (footprint "eagle-import:C050-025X075")
      (libsource (lib "eagle-import") (part "C-US050-025X075"))
    )
    (comp (ref "D2")
      (value "1N4148")
      (footprint "eagle-import:DO35-10")
      (libsource (lib "eagle-import") (part "1N4148DO35-10"))
    )
    (comp (ref "D4")
      (value "1N4148")
      (footprint "eagle-import:DO35-10")
      (libsource (lib "eagle-import") (part "1N4148DO35-10"))
    )
    (comp (ref "D5")
      (value "1N4148")
      (footprint "eagle-import:DO35-10")
      (libsource (lib "eagle-import") (part "1N4148DO35-10"))
    )
    (comp (ref "E8")
      (value "7400N")
      (footprint "eagle-import:DIL14")
      (libsource (lib "eagle-import") (part "7400N"))
    )
    (comp (ref "E11")
      (value "7410N")
      (footprint "eagle-import:DIL14")
      (libsource (lib "eagle-import") (part "7410N"))
    )
    (comp (ref "E12")
      (value "74S74N")
      (footprint "eagle-import:DIL14")
      (libsource (lib "eagle-import") (part "7474NS"))
    )
    (comp (ref "E21")
      (value "DS75453N")
      (footprint "eagle-import:DIL08")
      (libsource (lib "eagle-import") (part "DS75453N"))
    )
    (comp (ref "E22")
      (value "DS1100M-250")
      (footprint "eagle-import:DIL08")
      (libsource (lib "eagle-import") (part "MXD1000"))
    )
    (comp (ref "E24")
      (value "74S240N")
      (footprint "eagle-import:DIL20")
      (libsource (lib "eagle-import") (part "74240NS"))
    )
    (comp (ref "E28")
      (value "DS1005-250")
      (footprint "eagle-import:DIL14")
      (libsource (lib "eagle-import") (part "MXD1000P"))
    )
    (comp (ref "E30")
      (value "DS1005-250")
      (footprint "eagle-import:DIL14")
      (libsource (lib "eagle-import") (part "MXD1000P"))
    )
    (comp (ref "E31")
      (value "7400N")
      (footprint "eagle-import:DIL14")
      (libsource (lib "eagle-import") (part "7400N"))
    )
    (comp (ref "E35")
      (value "DS1100M-250")
      (footprint "eagle-import:DIL08")
      (libsource (lib "eagle-import") (part "MXD1000"))
    )
    (comp (ref "JP1")
      (value "JP2Q")
      (footprint "eagle-import:JP2Q")
      (libsource (lib "eagle-import") (part "JP2Q"))
    )
    (comp (ref "JP2")
      (value "JP3Q")
      (footprint "eagle-import:JP3Q")
      (libsource (lib "eagle-import") (part "JP3Q"))
    )
    (comp (ref "JP3")
      (value "JP2Q")
      (footprint "eagle-import:JP2Q")
      (libsource (lib "eagle-import") (part "JP2Q"))
    )
    (comp (ref "JP4")
      (value "JP3Q")
      (footprint "eagle-import:JP3Q")
      (libsource (lib "eagle-import") (part "JP3Q"))
    )
    (comp (ref "R15")
      (value "330")
      (footprint "eagle-import:0207_10")
      (libsource (lib "eagle-import") (part "R-US_0207/10"))
    )
    (comp (ref "R16")
      (value "750")
      (footprint "eagle-import:0207_10")
      (libsource (lib "eagle-import") (part "R-US_0207/10"))
    )
    (comp (ref "R17")
      (value "330")
      (footprint "eagle-import:0207_10")
      (libsource (lib "eagle-import") (part "R-US_0207/10"))
    )
    (comp (ref "R18")
      (value "750")
      (footprint "eagle-import:0207_10")
      (libsource (lib "eagle-import") (part "R-US_0207/10"))
    )
    (comp (ref "R21")
      (value "330")
      (footprint "eagle-import:0207_10")
      (libsource (lib "eagle-import") (part "R-US_0207/10"))
    )
    (comp (ref "R22")
      (value "330")
      (footprint "eagle-import:0207_10")
      (libsource (lib "eagle-import") (part "R-US_0207/10"))
    )
    (comp (ref "R27")
      (value "330")
      (footprint "eagle-import:0207_10")
      (libsource (lib "eagle-import") (part "R-US_0207/10"))
    )
    (comp (ref "R28")
      (value "330")
      (footprint "eagle-import:0207_10")
      (libsource (lib "eagle-import") (part "R-US_0207/10"))
    )
    (comp (ref "R29")
      (value "330")
      (footprint "eagle-import:0207_10")
      (libsource (lib "eagle-import") (part "R-US_0207/10"))
    )
    (comp (ref "R30")
      (value "330")
      (footprint "eagle-import:0207_10")
      (libsource (lib "eagle-import") (part "R-US_0207/10"))
    )
  )
  (nets
    (net (code "1") (name "B17S1") (class "Default")
      (node (ref "E12") (pin "4") (pinfunction "PRE_4") (pintype "input"))
      (node (ref "E39") (pin "1") (pinfunction "I0_1") (pintype "input"))
      (node (ref "E39") (pin "4") (pinfunction "I0_4") (pintype "input"))
      (node (ref "E39") (pin "9") (pinfunction "I0_9") (pintype "input"))
      (node (ref "E6") (pin "10") (pinfunction "PRE_10") (pintype "input"))
      (node (ref "E6") (pin "4") (pinfunction "PRE_4") (pintype "input"))
      (node (ref "E8") (pin "3") (pinfunction "O_3") (pintype "output"))
      (node (ref "E9") (pin "10") (pinfunction "PRE_10") (pintype "input"))
    )
    (net (code "2") (name "B17V1") (class "Default")
      (node (ref "E17") (pin "1") (pinfunction "CLR_1") (pintype "input"))
      (node (ref "E17") (pin "13") (pinfunction "CLR_13") (pintype "input"))
      (node (ref "E18") (pin "1") (pinfunction "CLR_1") (pintype "input"))
      (node (ref "E18") (pin "13") (pinfunction "CLR_13") (pintype "input"))
      (node (ref "E2") (pin "1") (pinfunction "CLR_1") (pintype "input"))
      (node (ref "E2") (pin "13") (pinfunction "CLR_13") (pintype "input"))
      (node (ref "E42") (pin "1") (pinfunction "CLR_1") (pintype "input"))
      (node (ref "E42") (pin "13") (pinfunction "CLR_13") (pintype "input"))
      (node (ref "E43") (pin "1") (pinfunction "CLR_1") (pintype "input"))
      (node (ref "E43") (pin "13") (pinfunction "CLR_13") (pintype "input"))
      (node (ref "E5") (pin "1") (pinfunction "CLR_1") (pintype "input"))
      (node (ref "E5") (pin "13") (pinfunction "CLR_13") (pintype "input"))
      (node (ref "E6") (pin "1") (pinfunction "CLR_1") (pintype "input"))
      (node (ref "E6") (pin "13") (pinfunction "CLR_13") (pintype "input"))
      (node (ref "E9") (pin "13") (pinfunction "CLR_13") (pintype "input"))
      (node (ref "R15") (pin "2") (pinfunction "2_2") (pintype "passive"))
      (node (ref "R16") (pin "1") (pinfunction "1_1") (pintype "passive"))
    )
    (net (code "3") (name "D01BINIT") (class "Default")
      (node (ref "E14") (pin "15") (pinfunction "A3_15") (pintype "input"))
      (node (ref "E14") (pin "17") (pinfunction "A4_17") (pintype "input"))
      (node (ref "E15") (pin "4") (pinfunction "O_4") (pintype "output"))
    )
    (net (code "4") (name "D01BTP2L") (class "Default")
      (node (ref "E15") (pin "2") (pinfunction "O_2") (pintype "output"))
      (node (ref "E3") (pin "13") (pinfunction "I2_13") (pintype "input"))
      (node (ref "E3") (pin "2") (pinfunction "I1_2") (pintype "input"))
      (node (ref "E9") (pin "4") (pinfunction "PRE_4") (pintype "input"))
    )
    (net (code "5") (name "D01DEL4") (class "Default")
      (node (ref "E11") (pin "3") (pinfunction "I0_3") (pintype "input"))
      (node (ref "E24") (pin "16") (pinfunction "Y2_16") (pintype "tri_state"))
      (node (ref "E29") (pin "1") (pinfunction "I0_1") (pintype "input"))
      (node (ref "E3") (pin "9") (pinfunction "I0_9") (pintype "input"))
    )
    (net (code "6") (name "D01DEL5") (class "Default")
      (node (ref "E11") (pin "9") (pinfunction "I0_9") (pintype "input"))
      (node (ref "E24") (pin "14") (pinfunction "Y3_14") (pintype "tri_state"))
      (node (ref "E9") (pin "3") (pinfunction "CLK_3") (pintype "input"))
    )
    (net (code "7") (name "D01DONEL") (class "Default")
      (node (ref "E11") (pin "8") (pinfunction "O_8") (pintype "output"))
      (node (ref "E21") (pin "6") (pinfunction "I1_6") (pintype "input"))
    )
    (net (code "8") (name "D01INITL") (class "Default")
      (node (ref "E12") (pin "1") (pinfunction "CLR_1") (pintype "input"))
      (node (ref "E12") (pin "13") (pinfunction "CLR_13") (pintype "input"))
      (node (ref "E14") (pin "3") (pinfunction "Y4_3") (pintype "tri_state"))
      (node (ref "E9") (pin "1") (pinfunction "CLR_1") (pintype "input"))
    )
    (net (code "9") (name "D01LOADMDL") (class "Default")
      (node (ref "E11") (pin "6") (pinfunction "O_6") (pintype "output"))
      (node (ref "E39") (pin "10") (pinfunction "I1_10") (pintype "input"))
      (node (ref "E39") (pin "2") (pinfunction "I1_2") (pintype "input"))
      (node (ref "E39") (pin "5") (pinfunction "I1_5") (pintype "input"))
    )
    (net (code "10") (name "D01MEMDONEL") (class "Default")
      (node (ref "E21") (pin "5") (pinfunction "O_5") (pintype "output"))
      (node (ref "H05/H24") (pin "28") (pinfunction "28_28") (pintype "passive"))
    )
    (net (code "11") (name "D01MEMSTARTL") (class "Default")
      (node (ref "E12") (pin "10") (pinfunction "PRE_10") (pintype "input"))
      (node (ref "E15") (pin "6") (pinfunction "O_6") (pintype "output"))
      (node (ref "E3") (pin "1") (pinfunction "I0_1") (pintype "input"))
    )
    (net (code "12") (name "D01POWEROK") (class "Default")
      (node (ref "E15") (pin "3") (pinfunction "I_3") (pintype "input"))
      (node (ref "E4") (pin "7") (pinfunction "RST_7") (pintype "output"))
    )
    (net (code "13") (name "D01READH") (class "Default")
      (node (ref "E11") (pin "4") (pinfunction "I1_4") (pintype "input"))
      (node (ref "E11") (pin "5") (pinfunction "I2_5") (pintype "input"))
      (node (ref "E12") (pin "9") (pinfunction "Q_9") (pintype "output"))
      (node (ref "E3") (pin "10") (pinfunction "I1_10") (pintype "input"))
      (node (ref "E3") (pin "11") (pinfunction "I2_11") (pintype "input"))
    )
    (net (code "14") (name "D01READL") (class "Default")
      (node (ref "E10") (pin "22") (pinfunction "~{OE}_22") (pintype "input"))
      (node (ref "E11") (pin "10") (pinfunction "I1_10") (pintype "input"))
      (node (ref "E11") (pin "11") (pinfunction "I2_11") (pintype "input"))
      (node (ref "E12") (pin "8") (pinfunction "~{Q}_8") (pintype "output"))
      (node (ref "E16") (pin "22") (pinfunction "~{OE}_22") (pintype "input"))
    )
    (net (code "15") (name "D01SELECTH") (class "Default")
      (node (ref "E12") (pin "6") (pinfunction "~{Q}_6") (pintype "output"))
      (node (ref "E14") (pin "13") (pinfunction "A2_13") (pintype "input"))
    )
    (net (code "16") (name "D01SELECTL") (class "Default")
      (node (ref "E12") (pin "5") (pinfunction "Q_5") (pintype "output"))
      (node (ref "E21") (pin "2") (pinfunction "I1_2") (pintype "input"))
      (node (ref "E21") (pin "7") (pinfunction "I0_7") (pintype "input"))
    )
    (net (code "17") (name "D01STROBEL") (class "Default")
      (node (ref "E21") (pin "3") (pinfunction "O_3") (pintype "output"))
      (node (ref "H05/H24") (pin "24") (pinfunction "24_24") (pintype "passive"))
      (node (ref "R17") (pin "2") (pinfunction "2_2") (pintype "passive"))
      (node (ref "R18") (pin "1") (pinfunction "1_1") (pintype "passive"))
    )
    (net (code "18") (name "D01WRITEH") (class "Default")
      (node (ref "E14") (pin "11") (pinfunction "A1_11") (pintype "input"))
      (node (ref "E9") (pin "5") (pinfunction "Q_5") (pintype "output"))
    )
    (net (code "19") (name "D01WRITEL") (class "Default")
      (node (ref "E10") (pin "27") (pinfunction "~{WE}_27") (pintype "input"))
      (node (ref "E14") (pin "9") (pinfunction "Y1_9") (pintype "tri_state"))
      (node (ref "E16") (pin "27") (pinfunction "~{WE}_27") (pintype "input"))
      (node (ref "E33") (pin "2") (pinfunction "I1_2") (pintype "input"))
      (node (ref "E33") (pin "6") (pinfunction "I1_6") (pintype "input"))
      (node (ref "E34") (pin "2") (pinfunction "I1_2") (pintype "input"))
      (node (ref "E34") (pin "6") (pinfunction "I1_6") (pintype "input"))
      (node (ref "E36") (pin "2") (pinfunction "I1_2") (pintype "input"))
      (node (ref "E36") (pin "6") (pinfunction "I1_6") (pintype "input"))
      (node (ref "E37") (pin "2") (pinfunction "I1_2") (pintype "input"))
      (node (ref "E37") (pin "6") (pinfunction "I1_6") (pintype "input"))
      (node (ref "E40") (pin "2") (pinfunction "I1_2") (pintype "input"))
      (node (ref "E40") (pin "6") (pinfunction "I1_6") (pintype "input"))
      (node (ref "E41") (pin "2") (pinfunction "I1_2") (pintype "input"))
      (node (ref "E41") (pin "6") (pinfunction "I1_6") (pintype "input"))
    )
    (net (code "20") (name "D02MEM0") (class "Default")
      (node (ref "E25") (pin "3") (pinfunction "O_3") (pintype "output"))
      (node (ref "H04/H23") (pin "8") (pinfunction "8_8") (pintype "passive"))
    )
    (net (code "21") (name "D02MEM1") (class "Default")
      (node (ref "E25") (pin "5") (pinfunction "O_5") (pintype "output"))
      (node (ref "H04/H23") (pin "12") (pinfunction "12_12") (pintype "passive"))
    )
    (net (code "22") (name "D02MEM2") (class "Default")
      (node (ref "E32") (pin "3") (pinfunction "O_3") (pintype "output"))
      (node (ref "H04/H23") (pin "16") (pinfunction "16_16") (pintype "passive"))
    )
    (net (code "23") (name "D02MEM3") (class "Default")
      (node (ref "E32") (pin "5") (pinfunction "O_5") (pintype "output"))
      (node (ref "H04/H23") (pin "20") (pinfunction "20_20") (pintype "passive"))
    )
    (net (code "24") (name "D02MEM4") (class "Default")
      (node (ref "E26") (pin "3") (pinfunction "O_3") (pintype "output"))
      (node (ref "H04/H23") (pin "24") (pinfunction "24_24") (pintype "passive"))
    )
    (net (code "25") (name "D02MEM5") (class "Default")
      (node (ref "E26") (pin "5") (pinfunction "O_5") (pintype "output"))
      (node (ref "H04/H23") (pin "28") (pinfunction "28_28") (pintype "passive"))
    )
    (net (code "26") (name "D02MEM6") (class "Default")
      (node (ref "E27") (pin "3") (pinfunction "O_3") (pintype "output"))
      (node (ref "H04/H23") (pin "30") (pinfunction "30_30") (pintype "passive"))
    )
    (net (code "27") (name "D02MEM7") (class "Default")
      (node (ref "E27") (pin "5") (pinfunction "O_5") (pintype "output"))
      (node (ref "H04/H23") (pin "32") (pinfunction "32_32") (pintype "passive"))
    )
    (net (code "28") (name "D02MEM8") (class "Default")
      (node (ref "E19") (pin "3") (pinfunction "O_3") (pintype "output"))
      (node (ref "H05/H24") (pin "6") (pinfunction "6_6") (pintype "passive"))
    )
    (net (code "29") (name "D02MEM9") (class "Default")
      (node (ref "E19") (pin "5") (pinfunction "O_5") (pintype "output"))
      (node (ref "H05/H24") (pin "8") (pinfunction "8_8") (pintype "passive"))
    )
    (net (code "30") (name "D02MEM10") (class "Default")
      (node (ref "E20") (pin "3") (pinfunction "O_3") (pintype "output"))
      (node (ref "H05/H24") (pin "12") (pinfunction "12_12") (pintype "passive"))
    )
    (net (code "31") (name "D02MEM11") (class "Default")
      (node (ref "E20") (pin "5") (pinfunction "O_5") (pintype "output"))
      (node (ref "H05/H24") (pin "16") (pinfunction "16_16") (pintype "passive"))
    )
    (net (code "32") (name "D03BEMA0L") (class "Default")
      (node (ref "E10") (pin "8") (pinfunction "A2_8") (pintype "input"))
      (node (ref "E16") (pin "8") (pinfunction "A2_8") (pintype "input"))
      (node (ref "E6") (pin "6") (pinfunction "~{Q}_6") (pintype "output"))
    )
    (net (code "33") (name "D03BEMA1L") (class "Default")
      (node (ref "E10") (pin "9") (pinfunction "A1_9") (pintype "input"))
      (node (ref "E16") (pin "9") (pinfunction "A1_9") (pintype "input"))
      (node (ref "E6") (pin "8") (pinfunction "~{Q}_8") (pintype "output"))
    )
    (net (code "34") (name "D03BEMA2L") (class "Default")
      (node (ref "E10") (pin "10") (pinfunction "A0_10") (pintype "input"))
      (node (ref "E16") (pin "10") (pinfunction "A0_10") (pintype "input"))
      (node (ref "E9") (pin "8") (pinfunction "~{Q}_8") (pintype "output"))
    )
    (net (code "35") (name "D03BMA0") (class "Default")
      (node (ref "E1") (pin "2") (pinfunction "A1_2") (pintype "input"))
      (node (ref "H01/H20") (pin "16") (pinfunction "16_16") (pintype "passive"))
    )
    (net (code "36") (name "D03BMA1") (class "Default")
      (node (ref "E1") (pin "4") (pinfunction "A2_4") (pintype "input"))
      (node (ref "H01/H20") (pin "20") (pinfunction "20_20") (pintype "passive"))
    )
    (net (code "37") (name "D03BMA2") (class "Default")
      (node (ref "E1") (pin "6") (pinfunction "A3_6") (pintype "input"))
      (node (ref "H01/H20") (pin "24") (pinfunction "24_24") (pintype "passive"))
    )
    (net (code "38") (name "D03BMA3") (class "Default")
      (node (ref "E1") (pin "8") (pinfunction "A4_8") (pintype "input"))
      (node (ref "H01/H20") (pin "28") (pinfunction "28_28") (pintype "passive"))
    )
    (net (code "39") (name "D03BMA4") (class "Default")
      (node (ref "E14") (pin "8") (pinfunction "A4_8") (pintype "input"))
      (node (ref "H01/H20") (pin "30") (pinfunction "30_30") (pintype "passive"))
    )
    (net (code "40") (name "D03BMA5") (class "Default")
      (node (ref "E14") (pin "6") (pinfunction "A3_6") (pintype "input"))
      (node (ref "H01/H20") (pin "32") (pinfunction "32_32") (pintype "passive"))
    )
    (net (code "41") (name "D03BMA6") (class "Default")
      (node (ref "E14") (pin "4") (pinfunction "A2_4") (pintype "input"))
      (node (ref "H02/H21") (pin "6") (pinfunction "6_6") (pintype "passive"))
    )
    (net (code "42") (name "D03BMA7") (class "Default")
      (node (ref "E14") (pin "2") (pinfunction "A1_2") (pintype "input"))
      (node (ref "H02/H21") (pin "8") (pinfunction "8_8") (pintype "passive"))
    )
    (net (code "43") (name "D03BMA8") (class "Default")
      (node (ref "E1") (pin "17") (pinfunction "A4_17") (pintype "input"))
      (node (ref "H02/H21") (pin "12") (pinfunction "12_12") (pintype "passive"))
    )
    (net (code "44") (name "D03BMA9") (class "Default")
      (node (ref "E1") (pin "15") (pinfunction "A3_15") (pintype "input"))
      (node (ref "H02/H21") (pin "16") (pinfunction "16_16") (pintype "passive"))
    )
    (net (code "45") (name "D03BMA10") (class "Default")
      (node (ref "E1") (pin "13") (pinfunction "A2_13") (pintype "input"))
      (node (ref "H02/H21") (pin "20") (pinfunction "20_20") (pintype "passive"))
    )
    (net (code "46") (name "D03BMA11") (class "Default")
      (node (ref "E1") (pin "11") (pinfunction "A1_11") (pintype "input"))
      (node (ref "H02/H21") (pin "24") (pinfunction "24_24") (pintype "passive"))
    )
    (net (code "47") (name "D03BTP2") (class "Default")
      (node (ref "E12") (pin "11") (pinfunction "CLK_11") (pintype "input"))
      (node (ref "E15") (pin "1") (pinfunction "I_1") (pintype "input"))
      (node (ref "H05/H24") (pin "32") (pinfunction "32_32") (pintype "passive"))
    )
    (net (code "48") (name "D03EA0") (class "Default")
      (node (ref "E38") (pin "2") (pinfunction "A1_2") (pintype "input"))
      (node (ref "H03/H22") (pin "6") (pinfunction "6_6") (pintype "passive"))
    )
    (net (code "49") (name "D03EA1") (class "Default")
      (node (ref "E38") (pin "4") (pinfunction "A2_4") (pintype "input"))
      (node (ref "H03/H22") (pin "8") (pinfunction "8_8") (pintype "passive"))
    )
    (net (code "50") (name "D03EA2") (class "Default")
      (node (ref "E38") (pin "6") (pinfunction "A3_6") (pintype "input"))
      (node (ref "H03/H22") (pin "12") (pinfunction "12_12") (pintype "passive"))
    )
    (net (code "51") (name "D03EMA0H") (class "Default")
      (node (ref "E6") (pin "2") (pinfunction "D_2") (pintype "input"))
      (node (ref "E7") (pin "8") (pinfunction "O_8") (pintype "output"))
      (node (ref "E8") (pin "9") (pinfunction "I0_9") (pintype "input"))
      (node (ref "JP1") (pin "1") (pinfunction "1_1") (pintype "passive"))
    )
    (net (code "52") (name "D03EMA0L") (class "Default")
      (node (ref "E38") (pin "18") (pinfunction "Y1_18") (pintype "tri_state"))
      (node (ref "E7") (pin "1") (pinfunction "I_1") (pintype "input"))
      (node (ref "E7") (pin "9") (pinfunction "I_9") (pintype "input"))
      (node (ref "E8") (pin "4") (pinfunction "I0_4") (pintype "input"))
      (node (ref "JP1") (pin "3") (pinfunction "3_3") (pintype "passive"))
    )
    (net (code "53") (name "D03EMA1H") (class "Default")
      (node (ref "E6") (pin "12") (pinfunction "D_12") (pintype "input"))
      (node (ref "E7") (pin "10") (pinfunction "O_10") (pintype "output"))
      (node (ref "E8") (pin "10") (pinfunction "I1_10") (pintype "input"))
      (node (ref "JP2") (pin "3") (pinfunction "3_3") (pintype "passive"))
    )
    (net (code "54") (name "D03EMA1L") (class "Default")
      (node (ref "E38") (pin "16") (pinfunction "Y2_16") (pintype "tri_state"))
      (node (ref "E7") (pin "11") (pinfunction "I_11") (pintype "input"))
      (node (ref "E8") (pin "5") (pinfunction "I1_5") (pintype "input"))
      (node (ref "JP2") (pin "1") (pinfunction "1_1") (pintype "passive"))
    )
    (net (code "55") (name "D03EMA2H") (class "Default")
      (node (ref "E7") (pin "12") (pinfunction "O_12") (pintype "output"))
      (node (ref "E9") (pin "12") (pinfunction "D_12") (pintype "input"))
      (node (ref "JP3") (pin "1") (pinfunction "1_1") (pintype "passive"))
    )
    (net (code "56") (name "D03EMA2L") (class "Default")
      (node (ref "E38") (pin "14") (pinfunction "Y3_14") (pintype "tri_state"))
      (node (ref "E7") (pin "13") (pinfunction "I_13") (pintype "input"))
      (node (ref "JP3") (pin "3") (pinfunction "3_3") (pintype "passive"))
    )
    (net (code "57") (name "D03MA0L") (class "Default")
      (node (ref "E1") (pin "18") (pinfunction "Y1_18") (pintype "tri_state"))
      (node (ref "E10") (pin "1") (pinfunction "A14_1") (pintype "input"))
      (node (ref "E16") (pin "1") (pinfunction "A14_1") (pintype "input"))
    )
    (net (code "58") (name "D03MA1L") (class "Default")
      (node (ref "E1") (pin "16") (pinfunction "Y2_16") (pintype "tri_state"))
      (node (ref "E10") (pin "26") (pinfunction "A13_26") (pintype "input"))
      (node (ref "E16") (pin "26") (pinfunction "A13_26") (pintype "input"))
    )
    (net (code "59") (name "D03MA2L") (class "Default")
      (node (ref "E1") (pin "14") (pinfunction "Y3_14") (pintype "tri_state"))
      (node (ref "E10") (pin "2") (pinfunction "A12_2") (pintype "input"))
      (node (ref "E16") (pin "2") (pinfunction "A12_2") (pintype "input"))
    )
    (net (code "60") (name "D03MA3L") (class "Default")
      (node (ref "E1") (pin "12") (pinfunction "Y4_12") (pintype "tri_state"))
      (node (ref "E10") (pin "23") (pinfunction "A11_23") (pintype "input"))
      (node (ref "E16") (pin "23") (pinfunction "A11_23") (pintype "input"))
    )
    (net (code "61") (name "D03MA4L") (class "Default")
      (node (ref "E10") (pin "21") (pinfunction "A10_21") (pintype "input"))
      (node (ref "E14") (pin "12") (pinfunction "Y4_12") (pintype "tri_state"))
      (node (ref "E16") (pin "21") (pinfunction "A10_21") (pintype "input"))
    )
    (net (code "62") (name "D03MA5L") (class "Default")
      (node (ref "E10") (pin "24") (pinfunction "A9_24") (pintype "input"))
      (node (ref "E14") (pin "14") (pinfunction "Y3_14") (pintype "tri_state"))
      (node (ref "E16") (pin "24") (pinfunction "A9_24") (pintype "input"))
    )
    (net (code "63") (name "D03MA6L") (class "Default")
      (node (ref "E10") (pin "25") (pinfunction "A8_25") (pintype "input"))
      (node (ref "E14") (pin "16") (pinfunction "Y2_16") (pintype "tri_state"))
      (node (ref "E16") (pin "25") (pinfunction "A8_25") (pintype "input"))
    )
    (net (code "64") (name "D03MA7L") (class "Default")
      (node (ref "E10") (pin "3") (pinfunction "A7_3") (pintype "input"))
      (node (ref "E14") (pin "18") (pinfunction "Y1_18") (pintype "tri_state"))
      (node (ref "E16") (pin "3") (pinfunction "A7_3") (pintype "input"))
    )
    (net (code "65") (name "D03MA8L") (class "Default")
      (node (ref "E1") (pin "3") (pinfunction "Y4_3") (pintype "tri_state"))
      (node (ref "E10") (pin "4") (pinfunction "A6_4") (pintype "input"))
      (node (ref "E16") (pin "4") (pinfunction "A6_4") (pintype "input"))
    )
    (net (code "66") (name "D03MA9L") (class "Default")
      (node (ref "E1") (pin "5") (pinfunction "Y3_5") (pintype "tri_state"))
      (node (ref "E10") (pin "5") (pinfunction "A5_5") (pintype "input"))
      (node (ref "E16") (pin "5") (pinfunction "A5_5") (pintype "input"))
    )
    (net (code "67") (name "D03MA10L") (class "Default")
      (node (ref "E1") (pin "7") (pinfunction "Y2_7") (pintype "tri_state"))
      (node (ref "E10") (pin "6") (pinfunction "A4_6") (pintype "input"))
      (node (ref "E16") (pin "6") (pinfunction "A4_6") (pintype "input"))
    )
    (net (code "68") (name "D03MA11L") (class "Default")
      (node (ref "E1") (pin "9") (pinfunction "Y1_9") (pintype "tri_state"))
      (node (ref "E10") (pin "7") (pinfunction "A3_7") (pintype "input"))
      (node (ref "E16") (pin "7") (pinfunction "A3_7") (pintype "input"))
    )
    (net (code "69") (name "D03MCBMB0L") (class "Default")
      (node (ref "E37") (pin "1") (pinfunction "I0_1") (pintype "input"))
      (node (ref "H02/H21") (pin "28") (pinfunction "28_28") (pintype "passive"))
    )
    (net (code "70") (name "D03MCBMB1L") (class "Default")
      (node (ref "E37") (pin "7") (pinfunction "I0_7") (pintype "input"))
      (node (ref "H02/H21") (pin "30") (pinfunction "30_30") (pintype "passive"))
    )
    (net (code "71") (name "D03MCBMB2L") (class "Default")
      (node (ref "E41") (pin "7") (pinfunction "I0_7") (pintype "input"))
      (node (ref "H02/H21") (pin "32") (pinfunction "32_32") (pintype "passive"))
    )
    (net (code "72") (name "D03MCBMB3L") (class "Default")
      (node (ref "E40") (pin "1") (pinfunction "I0_1") (pintype "input"))
      (node (ref "H01/H20") (pin "6") (pinfunction "6_6") (pintype "passive"))
    )
    (net (code "73") (name "D03MCBMB4L") (class "Default")
      (node (ref "E40") (pin "7") (pinfunction "I0_7") (pintype "input"))
      (node (ref "H01/H20") (pin "8") (pinfunction "8_8") (pintype "passive"))
    )
    (net (code "74") (name "D03MCBMB5L") (class "Default")
      (node (ref "E41") (pin "1") (pinfunction "I0_1") (pintype "input"))
      (node (ref "H01/H20") (pin "12") (pinfunction "12_12") (pintype "passive"))
    )
    (net (code "75") (name "D03MCBMB6L") (class "Default")
      (node (ref "E36") (pin "1") (pinfunction "I0_1") (pintype "input"))
      (node (ref "H03/H22") (pin "16") (pinfunction "16_16") (pintype "passive"))
    )
    (net (code "76") (name "D03MCBMB7L") (class "Default")
      (node (ref "E36") (pin "7") (pinfunction "I0_7") (pintype "input"))
      (node (ref "H03/H22") (pin "20") (pinfunction "20_20") (pintype "passive"))
    )
    (net (code "77") (name "D03MCBMB8L") (class "Default")
      (node (ref "E33") (pin "1") (pinfunction "I0_1") (pintype "input"))
      (node (ref "H03/H22") (pin "24") (pinfunction "24_24") (pintype "passive"))
    )
    (net (code "78") (name "D03MCBMB9L") (class "Default")
      (node (ref "E33") (pin "7") (pinfunction "I0_7") (pintype "input"))
      (node (ref "H03/H22") (pin "28") (pinfunction "28_28") (pintype "passive"))
    )
    (net (code "79") (name "D03MCBMB10L") (class "Default")
      (node (ref "E34") (pin "1") (pinfunction "I0_1") (pintype "input"))
      (node (ref "H03/H22") (pin "30") (pinfunction "30_30") (pintype "passive"))
    )
    (net (code "80") (name "D03MCBMB11L") (class "Default")
      (node (ref "E34") (pin "7") (pinfunction "I0_7") (pintype "input"))
      (node (ref "H03/H22") (pin "32") (pinfunction "32_32") (pintype "passive"))
    )
    (net (code "81") (name "D03MEMSTART") (class "Default")
      (node (ref "E12") (pin "3") (pinfunction "CLK_3") (pintype "input"))
      (node (ref "E15") (pin "5") (pinfunction "I_5") (pintype "input"))
      (node (ref "E6") (pin "11") (pinfunction "CLK_11") (pintype "input"))
      (node (ref "E6") (pin "3") (pinfunction "CLK_3") (pintype "input"))
      (node (ref "E9") (pin "11") (pinfunction "CLK_11") (pintype "input"))
      (node (ref "H05/H24") (pin "20") (pinfunction "20_20") (pintype "passive"))
    )
    (net (code "82") (name "D04MD0L") (class "Default")
      (node (ref "E16") (pin "11") (pinfunction "I/O0_11") (pintype "bidirectional"))
      (node (ref "E2") (pin "12") (pinfunction "D_12") (pintype "input"))
      (node (ref "E37") (pin "3") (pinfunction "O_3") (pintype "output"))
    )
    (net (code "83") (name "D04MD1L") (class "Default")
      (node (ref "E16") (pin "12") (pinfunction "I/O1_12") (pintype "bidirectional"))
      (node (ref "E2") (pin "2") (pinfunction "D_2") (pintype "input"))
      (node (ref "E37") (pin "5") (pinfunction "O_5") (pintype "output"))
    )
    (net (code "84") (name "D04MD2L") (class "Default")
      (node (ref "E16") (pin "13") (pinfunction "I/O2_13") (pintype "bidirectional"))
      (node (ref "E41") (pin "5") (pinfunction "O_5") (pintype "output"))
      (node (ref "E5") (pin "12") (pinfunction "D_12") (pintype "input"))
    )
    (net (code "85") (name "D04MD3L") (class "Default")
      (node (ref "E16") (pin "15") (pinfunction "I/O3_15") (pintype "bidirectional"))
      (node (ref "E40") (pin "3") (pinfunction "O_3") (pintype "output"))
      (node (ref "E5") (pin "2") (pinfunction "D_2") (pintype "input"))
    )
    (net (code "86") (name "D04MD4L") (class "Default")
      (node (ref "E16") (pin "16") (pinfunction "I/O4_16") (pintype "bidirectional"))
      (node (ref "E17") (pin "12") (pinfunction "D_12") (pintype "input"))
      (node (ref "E40") (pin "5") (pinfunction "O_5") (pintype "output"))
    )
    (net (code "87") (name "D04MD5L") (class "Default")
      (node (ref "E16") (pin "17") (pinfunction "I/O5_17") (pintype "bidirectional"))
      (node (ref "E17") (pin "2") (pinfunction "D_2") (pintype "input"))
      (node (ref "E41") (pin "3") (pinfunction "O_3") (pintype "output"))
    )
    (net (code "88") (name "D04MD6L") (class "Default")
      (node (ref "E10") (pin "11") (pinfunction "I/O0_11") (pintype "bidirectional"))
      (node (ref "E18") (pin "12") (pinfunction "D_12") (pintype "input"))
      (node (ref "E36") (pin "3") (pinfunction "O_3") (pintype "output"))
    )
    (net (code "89") (name "D04MD7L") (class "Default")
      (node (ref "E10") (pin "12") (pinfunction "I/O1_12") (pintype "bidirectional"))
      (node (ref "E18") (pin "2") (pinfunction "D_2") (pintype "input"))
      (node (ref "E36") (pin "5") (pinfunction "O_5") (pintype "output"))
    )
    (net (code "90") (name "D04MD8L") (class "Default")
      (node (ref "E10") (pin "13") (pinfunction "I/O2_13") (pintype "bidirectional"))
      (node (ref "E33") (pin "3") (pinfunction "O_3") (pintype "output"))
      (node (ref "E43") (pin "12") (pinfunction "D_12") (pintype "input"))
    )
    (net (code "91") (name "D04MD9L") (class "Default")
      (node (ref "E10") (pin "15") (pinfunction "I/O3_15") (pintype "bidirectional"))
      (node (ref "E33") (pin "5") (pinfunction "O_5") (pintype "output"))
      (node (ref "E43") (pin "2") (pinfunction "D_2") (pintype "input"))
    )
    (net (code "92") (name "D04MD10L") (class "Default")
      (node (ref "E10") (pin "16") (pinfunction "I/O4_16") (pintype "bidirectional"))
      (node (ref "E34") (pin "3") (pinfunction "O_3") (pintype "output"))
      (node (ref "E42") (pin "12") (pinfunction "D_12") (pintype "input"))
    )
    (net (code "93") (name "D04MD11L") (class "Default")
      (node (ref "E10") (pin "17") (pinfunction "I/O5_17") (pintype "bidirectional"))
      (node (ref "E34") (pin "5") (pinfunction "O_5") (pintype "output"))
      (node (ref "E42") (pin "2") (pinfunction "D_2") (pintype "input"))
    )
    (net (code "94") (name "GND") (class "Default")
      (node (ref "C10") (pin "2") (pinfunction "2_2") (pintype "passive"))
      (node (ref "C11") (pin "2") (pinfunction "2_2") (pintype "passive"))
      (node (ref "C12") (pin "2") (pinfunction "2_2") (pintype "passive"))
      (node (ref "C13") (pin "2") (pinfunction "2_2") (pintype "passive"))
      (node (ref "C14") (pin "2") (pinfunction "2_2") (pintype "passive"))
      (node (ref "C15") (pin "2") (pinfunction "2_2") (pintype "passive"))
      (node (ref "C16") (pin "2") (pinfunction "2_2") (pintype "passive"))
      (node (ref "C17") (pin "2") (pinfunction "2_2") (pintype "passive"))
      (node (ref "C18") (pin "2") (pinfunction "2_2") (pintype "passive"))
      (node (ref "C19") (pin "2") (pinfunction "2_2") (pintype "passive"))
      (node (ref "C20") (pin "2") (pinfunction "2_2") (pintype "passive"))
      (node (ref "C21") (pin "2") (pinfunction "2_2") (pintype "passive"))
      (node (ref "C22") (pin "2") (pinfunction "2_2") (pintype "passive"))
      (node (ref "C23") (pin "2") (pinfunction "2_2") (pintype "passive"))
      (node (ref "C24") (pin "2") (pinfunction "2_2") (pintype "passive"))
      (node (ref "C25") (pin "2") (pinfunction "2_2") (pintype "passive"))
      (node (ref "C26") (pin "2") (pinfunction "2_2") (pintype "passive"))
      (node (ref "C27") (pin "2") (pinfunction "2_2") (pintype "passive"))
      (node (ref "C28") (pin "2") (pinfunction "2_2") (pintype "passive"))
      (node (ref "C29") (pin "2") (pinfunction "2_2") (pintype "passive"))
      (node (ref "C30") (pin "2") (pinfunction "2_2") (pintype "passive"))
      (node (ref "C31") (pin "2") (pinfunction "2_2") (pintype "passive"))
      (node (ref "C32") (pin "2") (pinfunction "2_2") (pintype "passive"))
      (node (ref "C33") (pin "2") (pinfunction "2_2") (pintype "passive"))
      (node (ref "C34") (pin "2") (pinfunction "2_2") (pintype "passive"))
      (node (ref "C35") (pin "2") (pinfunction "2_2") (pintype "passive"))
      (node (ref "C36") (pin "2") (pinfunction "2_2") (pintype "passive"))
      (node (ref "C37") (pin "2") (pinfunction "2_2") (pintype "passive"))
      (node (ref "C38") (pin "2") (pinfunction "2_2") (pintype "passive"))
      (node (ref "C39") (pin "2") (pinfunction "2_2") (pintype "passive"))
      (node (ref "C40") (pin "2") (pinfunction "2_2") (pintype "passive"))
      (node (ref "C41") (pin "2") (pinfunction "2_2") (pintype "passive"))
      (node (ref "C42") (pin "2") (pinfunction "2_2") (pintype "passive"))
      (node (ref "C43") (pin "2") (pinfunction "2_2") (pintype "passive"))
      (node (ref "C44") (pin "2") (pinfunction "2_2") (pintype "passive"))
      (node (ref "C45") (pin "2") (pinfunction "2_2") (pintype "passive"))
      (node (ref "C46") (pin "2") (pinfunction "2_2") (pintype "passive"))
      (node (ref "C47") (pin "2") (pinfunction "2_2") (pintype "passive"))
      (node (ref "C48") (pin "2") (pinfunction "2_2") (pintype "passive"))
      (node (ref "C49") (pin "-") (pinfunction "-_-") (pintype "passive"))
      (node (ref "C50") (pin "-") (pinfunction "-_-") (pintype "passive"))
      (node (ref "C51") (pin "-") (pinfunction "-_-") (pintype "passive"))
      (node (ref "C52") (pin "-") (pinfunction "-_-") (pintype "passive"))
      (node (ref "C6") (pin "2") (pinfunction "2_2") (pintype "passive"))
      (node (ref "C7") (pin "2") (pinfunction "2_2") (pintype "passive"))
      (node (ref "C8") (pin "2") (pinfunction "2_2") (pintype "passive"))
      (node (ref "C9") (pin "2") (pinfunction "2_2") (pintype "passive"))
      (node (ref "D2") (pin "A") (pinfunction "A_A") (pintype "passive"))
      (node (ref "D4") (pin "A") (pinfunction "A_A") (pintype "passive"))
      (node (ref "D5") (pin "A") (pinfunction "A_A") (pintype "passive"))
      (node (ref "E1") (pin "1") (pinfunction "G_1") (pintype "input"))
      (node (ref "E1") (pin "19") (pinfunction "G_19") (pintype "input"))
      (node (ref "E10") (pin "14") (pinfunction "VSS_14") (pintype "power_in"))
      (node (ref "E10") (pin "20") (pinfunction "~{CS}_20") (pintype "input"))
      (node (ref "E12") (pin "12") (pinfunction "D_12") (pintype "input"))
      (node (ref "E14") (pin "1") (pinfunction "G_1") (pintype "input"))
      (node (ref "E14") (pin "19") (pinfunction "G_19") (pintype "input"))
      (node (ref "E16") (pin "14") (pinfunction "VSS_14") (pintype "power_in"))
      (node (ref "E16") (pin "20") (pinfunction "~{CS}_20") (pintype "input"))
      (node (ref "E24") (pin "1") (pinfunction "G_1") (pintype "input"))
      (node (ref "E24") (pin "11") (pinfunction "A1_11") (pintype "input"))
      (node (ref "E24") (pin "15") (pinfunction "A3_15") (pintype "input"))
      (node (ref "E24") (pin "17") (pinfunction "A4_17") (pintype "input"))
      (node (ref "E24") (pin "19") (pinfunction "G_19") (pintype "input"))
      (node (ref "E24") (pin "2") (pinfunction "A1_2") (pintype "input"))
      (node (ref "E24") (pin "8") (pinfunction "A4_8") (pintype "input"))
      (node (ref "E38") (pin "1") (pinfunction "G_1") (pintype "input"))
      (node (ref "E38") (pin "8") (pinfunction "A4_8") (pintype "input"))
      (node (ref "E4") (pin "1") (pinfunction "MR_1") (pintype "input"))
      (node (ref "E4") (pin "3") (pinfunction "GND_3") (pintype "power_in"))
      (node (ref "E8") (pin "1") (pinfunction "I0_1") (pintype "input"))
      (node (ref "E8") (pin "2") (pinfunction "I1_2") (pintype "input"))
      (node (ref "E9") (pin "2") (pinfunction "D_2") (pintype "input"))
      (node (ref "GND") (pin "1") (pinfunction "P_1") (pintype "passive"))
      (node (ref "H01/H20") (pin "1") (pinfunction "1_1") (pintype "passive"))
      (node (ref "H01/H20") (pin "11") (pinfunction "11_11") (pintype "passive"))
      (node (ref "H01/H20") (pin "13") (pinfunction "13_13") (pintype "passive"))
      (node (ref "H01/H20") (pin "15") (pinfunction "15_15") (pintype "passive"))
      (node (ref "H01/H20") (pin "17") (pinfunction "17_17") (pintype "passive"))
      (node (ref "H01/H20") (pin "19") (pinfunction "19_19") (pintype "passive"))
      (node (ref "H01/H20") (pin "21") (pinfunction "21_21") (pintype "passive"))
      (node (ref "H01/H20") (pin "23") (pinfunction "23_23") (pintype "passive"))
      (node (ref "H01/H20") (pin "25") (pinfunction "25_25") (pintype "passive"))
      (node (ref "H01/H20") (pin "27") (pinfunction "27_27") (pintype "passive"))
      (node (ref "H01/H20") (pin "29") (pinfunction "29_29") (pintype "passive"))
      (node (ref "H01/H20") (pin "3") (pinfunction "3_3") (pintype "passive"))
      (node (ref "H01/H20") (pin "31") (pinfunction "31_31") (pintype "passive"))
      (node (ref "H01/H20") (pin "33") (pinfunction "33_33") (pintype "passive"))
      (node (ref "H01/H20") (pin "5") (pinfunction "5_5") (pintype "passive"))
      (node (ref "H01/H20") (pin "7") (pinfunction "7_7") (pintype "passive"))
      (node (ref "H01/H20") (pin "9") (pinfunction "9_9") (pintype "passive"))
      (node (ref "H02/H21") (pin "1") (pinfunction "1_1") (pintype "passive"))
      (node (ref "H02/H21") (pin "11") (pinfunction "11_11") (pintype "passive"))
      (node (ref "H02/H21") (pin "13") (pinfunction "13_13") (pintype "passive"))
      (node (ref "H02/H21") (pin "15") (pinfunction "15_15") (pintype "passive"))
      (node (ref "H02/H21") (pin "17") (pinfunction "17_17") (pintype "passive"))
      (node (ref "H02/H21") (pin "19") (pinfunction "19_19") (pintype "passive"))
      (node (ref "H02/H21") (pin "21") (pinfunction "21_21") (pintype "passive"))
      (node (ref "H02/H21") (pin "23") (pinfunction "23_23") (pintype "passive"))
      (node (ref "H02/H21") (pin "25") (pinfunction "25_25") (pintype "passive"))
      (node (ref "H02/H21") (pin "27") (pinfunction "27_27") (pintype "passive"))
      (node (ref "H02/H21") (pin "29") (pinfunction "29_29") (pintype "passive"))
      (node (ref "H02/H21") (pin "3") (pinfunction "3_3") (pintype "passive"))
      (node (ref "H02/H21") (pin "31") (pinfunction "31_31") (pintype "passive"))
      (node (ref "H02/H21") (pin "33") (pinfunction "33_33") (pintype "passive"))
      (node (ref "H02/H21") (pin "5") (pinfunction "5_5") (pintype "passive"))
      (node (ref "H02/H21") (pin "7") (pinfunction "7_7") (pintype "passive"))
      (node (ref "H02/H21") (pin "9") (pinfunction "9_9") (pintype "passive"))
      (node (ref "H03/H22") (pin "1") (pinfunction "1_1") (pintype "passive"))
      (node (ref "H03/H22") (pin "11") (pinfunction "11_11") (pintype "passive"))
      (node (ref "H03/H22") (pin "13") (pinfunction "13_13") (pintype "passive"))
      (node (ref "H03/H22") (pin "15") (pinfunction "15_15") (pintype "passive"))
      (node (ref "H03/H22") (pin "17") (pinfunction "17_17") (pintype "passive"))
      (node (ref "H03/H22") (pin "19") (pinfunction "19_19") (pintype "passive"))
      (node (ref "H03/H22") (pin "21") (pinfunction "21_21") (pintype "passive"))
      (node (ref "H03/H22") (pin "23") (pinfunction "23_23") (pintype "passive"))
      (node (ref "H03/H22") (pin "25") (pinfunction "25_25") (pintype "passive"))
      (node (ref "H03/H22") (pin "27") (pinfunction "27_27") (pintype "passive"))
      (node (ref "H03/H22") (pin "29") (pinfunction "29_29") (pintype "passive"))
      (node (ref "H03/H22") (pin "3") (pinfunction "3_3") (pintype "passive"))
      (node (ref "H03/H22") (pin "31") (pinfunction "31_31") (pintype "passive"))
      (node (ref "H03/H22") (pin "33") (pinfunction "33_33") (pintype "passive"))
      (node (ref "H03/H22") (pin "5") (pinfunction "5_5") (pintype "passive"))
      (node (ref "H03/H22") (pin "7") (pinfunction "7_7") (pintype "passive"))
      (node (ref "H03/H22") (pin "9") (pinfunction "9_9") (pintype "passive"))
      (node (ref "H04/H23") (pin "1") (pinfunction "1_1") (pintype "passive"))
      (node (ref "H04/H23") (pin "11") (pinfunction "11_11") (pintype "passive"))
      (node (ref "H04/H23") (pin "13") (pinfunction "13_13") (pintype "passive"))
      (node (ref "H04/H23") (pin "15") (pinfunction "15_15") (pintype "passive"))
      (node (ref "H04/H23") (pin "17") (pinfunction "17_17") (pintype "passive"))
      (node (ref "H04/H23") (pin "19") (pinfunction "19_19") (pintype "passive"))
      (node (ref "H04/H23") (pin "21") (pinfunction "21_21") (pintype "passive"))
      (node (ref "H04/H23") (pin "23") (pinfunction "23_23") (pintype "passive"))
      (node (ref "H04/H23") (pin "25") (pinfunction "25_25") (pintype "passive"))
      (node (ref "H04/H23") (pin "27") (pinfunction "27_27") (pintype "passive"))
      (node (ref "H04/H23") (pin "29") (pinfunction "29_29") (pintype "passive"))
      (node (ref "H04/H23") (pin "3") (pinfunction "3_3") (pintype "passive"))
      (node (ref "H04/H23") (pin "31") (pinfunction "31_31") (pintype "passive"))
      (node (ref "H04/H23") (pin "33") (pinfunction "33_33") (pintype "passive"))
      (node (ref "H04/H23") (pin "5") (pinfunction "5_5") (pintype "passive"))
      (node (ref "H04/H23") (pin "7") (pinfunction "7_7") (pintype "passive"))
      (node (ref "H04/H23") (pin "9") (pinfunction "9_9") (pintype "passive"))
      (node (ref "H05/H24") (pin "1") (pinfunction "1_1") (pintype "passive"))
      (node (ref "H05/H24") (pin "11") (pinfunction "11_11") (pintype "passive"))
      (node (ref "H05/H24") (pin "13") (pinfunction "13_13") (pintype "passive"))
      (node (ref "H05/H24") (pin "15") (pinfunction "15_15") (pintype "passive"))
      (node (ref "H05/H24") (pin "17") (pinfunction "17_17") (pintype "passive"))
      (node (ref "H05/H24") (pin "19") (pinfunction "19_19") (pintype "passive"))
      (node (ref "H05/H24") (pin "21") (pinfunction "21_21") (pintype "passive"))
      (node (ref "H05/H24") (pin "23") (pinfunction "23_23") (pintype "passive"))
      (node (ref "H05/H24") (pin "25") (pinfunction "25_25") (pintype "passive"))
      (node (ref "H05/H24") (pin "27") (pinfunction "27_27") (pintype "passive"))
      (node (ref "H05/H24") (pin "29") (pinfunction "29_29") (pintype "passive"))
      (node (ref "H05/H24") (pin "3") (pinfunction "3_3") (pintype "passive"))
      (node (ref "H05/H24") (pin "31") (pinfunction "31_31") (pintype "passive"))
      (node (ref "H05/H24") (pin "33") (pinfunction "33_33") (pintype "passive"))
      (node (ref "H05/H24") (pin "5") (pinfunction "5_5") (pintype "passive"))
      (node (ref "H05/H24") (pin "7") (pinfunction "7_7") (pintype "passive"))
      (node (ref "H05/H24") (pin "9") (pinfunction "9_9") (pintype "passive"))
      (node (ref "JP2") (pin "5") (pinfunction "5_5") (pintype "passive"))
      (node (ref "R16") (pin "2") (pinfunction "2_2") (pintype "passive"))
      (node (ref "R18") (pin "2") (pinfunction "2_2") (pintype "passive"))
      (node (ref "R21") (pin "1") (pinfunction "1_1") (pintype "passive"))
      (node (ref "R27") (pin "1") (pinfunction "1_1") (pintype "passive"))
      (node (ref "R29") (pin "1") (pinfunction "1_1") (pintype "passive"))
    )
    (net (code "95") (name "Net-(E2A-CLK)") (class "Default")
      (node (ref "E2") (pin "11") (pinfunction "CLK_11") (pintype "input"))
      (node (ref "E2") (pin "3") (pinfunction "CLK_3") (pintype "input"))
      (node (ref "E39") (pin "3") (pinfunction "O_3") (pintype "output"))
      (node (ref "E5") (pin "11") (pinfunction "CLK_11") (pintype "input"))
      (node (ref "E5") (pin "3") (pinfunction "CLK_3") (pintype "input"))
    )
    (net (code "96") (name "Net-(E3B-I0)") (class "Default")
      (node (ref "E3") (pin "3") (pinfunction "I0_3") (pintype "input"))
      (node (ref "PAD27") (pin "1") (pinfunction "P_1") (pintype "passive"))
    )
    (net (code "97") (name "Net-(E3B-I1)") (class "Default")
      (node (ref "E3") (pin "4") (pinfunction "I1_4") (pintype "input"))
      (node (ref "PAD28") (pin "1") (pinfunction "P_1") (pintype "passive"))
    )
    (net (code "98") (name "Net-(E3B-I2)") (class "Default")
      (node (ref "E3") (pin "5") (pinfunction "I2_5") (pintype "input"))
      (node (ref "PAD29") (pin "1") (pinfunction "P_1") (pintype "passive"))
    )
    (net (code "99") (name "Net-(E3B-O)") (class "Default")
      (node (ref "E3") (pin "6") (pinfunction "O_6") (pintype "output"))
      (node (ref "PAD30") (pin "1") (pinfunction "P_1") (pintype "passive"))
    )
    (net (code "100") (name "Net-(E7A-O)") (class "Default")
      (node (ref "E7") (pin "2") (pinfunction "O_2") (pintype "output"))
      (node (ref "JP4") (pin "3") (pinfunction "3_3") (pintype "passive"))
    )
    (net (code "101") (name "Net-(E7B-I)") (class "Default")
      (node (ref "E7") (pin "3") (pinfunction "I_3") (pintype "input"))
      (node (ref "E8") (pin "8") (pinfunction "O_8") (pintype "output"))
    )
    (net (code "102") (name "Net-(E7B-O)") (class "Default")
      (node (ref "E7") (pin "4") (pinfunction "O_4") (pintype "output"))
      (node (ref "JP4") (pin "5") (pinfunction "5_5") (pintype "passive"))
    )
    (net (code "103") (name "Net-(E7C-I)") (class "Default")
      (node (ref "E7") (pin "5") (pinfunction "I_5") (pintype "input"))
      (node (ref "PAD1") (pin "1") (pinfunction "P_1") (pintype "passive"))
    )
    (net (code "104") (name "Net-(E7C-O)") (class "Default")
      (node (ref "E7") (pin "6") (pinfunction "O_6") (pintype "output"))
      (node (ref "PAD2") (pin "1") (pinfunction "P_1") (pintype "passive"))
    )
    (net (code "105") (name "Net-(E8B-O)") (class "Default")
      (node (ref "E8") (pin "6") (pinfunction "O_6") (pintype "output"))
      (node (ref "JP4") (pin "1") (pinfunction "1_1") (pintype "passive"))
    )
    (net (code "106") (name "Net-(E8D-I1)") (class "Default")
      (node (ref "E8") (pin "13") (pinfunction "I1_13") (pintype "input"))
      (node (ref "JP4") (pin "2") (pinfunction "2_2") (pintype "passive"))
      (node (ref "JP4") (pin "4") (pinfunction "4_4") (pintype "passive"))
      (node (ref "JP4") (pin "6") (pinfunction "6_6") (pintype "passive"))
    )
    (net (code "107") (name "Net-(E11A-I0)") (class "Default")
      (node (ref "E11") (pin "1") (pinfunction "I0_1") (pintype "input"))
      (node (ref "JP1") (pin "2") (pinfunction "2_2") (pintype "passive"))
      (node (ref "JP1") (pin "4") (pinfunction "4_4") (pintype "passive"))
    )
    (net (code "108") (name "Net-(E11A-I1)") (class "Default")
      (node (ref "E11") (pin "2") (pinfunction "I1_2") (pintype "input"))
      (node (ref "JP2") (pin "2") (pinfunction "2_2") (pintype "passive"))
      (node (ref "JP2") (pin "4") (pinfunction "4_4") (pintype "passive"))
      (node (ref "JP2") (pin "6") (pinfunction "6_6") (pintype "passive"))
    )
    (net (code "109") (name "Net-(E11A-I2)") (class "Default")
      (node (ref "E11") (pin "13") (pinfunction "I2_13") (pintype "input"))
      (node (ref "JP3") (pin "2") (pinfunction "2_2") (pintype "passive"))
      (node (ref "JP3") (pin "4") (pinfunction "4_4") (pintype "passive"))
    )
    (net (code "110") (name "Net-(E11A-O)") (class "Default")
      (node (ref "E11") (pin "12") (pinfunction "O_12") (pintype "output"))
      (node (ref "E8") (pin "12") (pinfunction "I0_12") (pintype "input"))
    )
    (net (code "111") (name "Net-(E12A-D)") (class "Default")
      (node (ref "E12") (pin "2") (pinfunction "D_2") (pintype "input"))
      (node (ref "E8") (pin "11") (pinfunction "O_11") (pintype "output"))
    )
    (net (code "112") (name "Net-(E14B-Y2)") (class "Default")
      (node (ref "E14") (pin "7") (pinfunction "Y2_7") (pintype "tri_state"))
      (node (ref "E19") (pin "2") (pinfunction "I1_2") (pintype "input"))
      (node (ref "E19") (pin "6") (pinfunction "I1_6") (pintype "input"))
      (node (ref "E20") (pin "2") (pinfunction "I1_2") (pintype "input"))
      (node (ref "E20") (pin "6") (pinfunction "I1_6") (pintype "input"))
      (node (ref "E25") (pin "2") (pinfunction "I1_2") (pintype "input"))
      (node (ref "E25") (pin "6") (pinfunction "I1_6") (pintype "input"))
      (node (ref "E26") (pin "2") (pinfunction "I1_2") (pintype "input"))
      (node (ref "E26") (pin "6") (pinfunction "I1_6") (pintype "input"))
      (node (ref "E27") (pin "2") (pinfunction "I1_2") (pintype "input"))
      (node (ref "E27") (pin "6") (pinfunction "I1_6") (pintype "input"))
      (node (ref "E32") (pin "2") (pinfunction "I1_2") (pintype "input"))
      (node (ref "E32") (pin "6") (pinfunction "I1_6") (pintype "input"))
    )
    (net (code "113") (name "Net-(E14B-Y3)") (class "Default")
      (node (ref "E14") (pin "5") (pinfunction "Y3_5") (pintype "tri_state"))
      (node (ref "E17") (pin "10") (pinfunction "PRE_10") (pintype "input"))
      (node (ref "E17") (pin "4") (pinfunction "PRE_4") (pintype "input"))
      (node (ref "E18") (pin "10") (pinfunction "PRE_10") (pintype "input"))
      (node (ref "E18") (pin "4") (pinfunction "PRE_4") (pintype "input"))
      (node (ref "E2") (pin "10") (pinfunction "PRE_10") (pintype "input"))
      (node (ref "E2") (pin "4") (pinfunction "PRE_4") (pintype "input"))
      (node (ref "E42") (pin "10") (pinfunction "PRE_10") (pintype "input"))
      (node (ref "E42") (pin "4") (pinfunction "PRE_4") (pintype "input"))
      (node (ref "E43") (pin "10") (pinfunction "PRE_10") (pintype "input"))
      (node (ref "E43") (pin "4") (pinfunction "PRE_4") (pintype "input"))
      (node (ref "E5") (pin "10") (pinfunction "PRE_10") (pintype "input"))
      (node (ref "E5") (pin "4") (pinfunction "PRE_4") (pintype "input"))
    )
    (net (code "114") (name "Net-(E15D-I)") (class "Default")
      (node (ref "E15") (pin "9") (pinfunction "I_9") (pintype "input"))
      (node (ref "PAD3") (pin "1") (pinfunction "P_1") (pintype "passive"))
    )
    (net (code "115") (name "Net-(E15D-O)") (class "Default")
      (node (ref "E15") (pin "8") (pinfunction "O_8") (pintype "output"))
      (node (ref "PAD4") (pin "1") (pinfunction "P_1") (pintype "passive"))
    )
    (net (code "116") (name "Net-(E15E-I)") (class "Default")
      (node (ref "E15") (pin "11") (pinfunction "I_11") (pintype "input"))
      (node (ref "PAD12") (pin "1") (pinfunction "P_1") (pintype "passive"))
    )
    (net (code "117") (name "Net-(E15E-O)") (class "Default")
      (node (ref "E15") (pin "10") (pinfunction "O_10") (pintype "output"))
      (node (ref "PAD13") (pin "1") (pinfunction "P_1") (pintype "passive"))
    )
    (net (code "118") (name "Net-(E15F-I)") (class "Default")
      (node (ref "E15") (pin "13") (pinfunction "I_13") (pintype "input"))
      (node (ref "PAD14") (pin "1") (pinfunction "P_1") (pintype "passive"))
    )
    (net (code "119") (name "Net-(E15F-O)") (class "Default")
      (node (ref "E15") (pin "12") (pinfunction "O_12") (pintype "output"))
      (node (ref "PAD15") (pin "1") (pinfunction "P_1") (pintype "passive"))
    )
    (net (code "120") (name "Net-(E17A-CLK)") (class "Default")
      (node (ref "E17") (pin "11") (pinfunction "CLK_11") (pintype "input"))
      (node (ref "E17") (pin "3") (pinfunction "CLK_3") (pintype "input"))
      (node (ref "E18") (pin "11") (pinfunction "CLK_11") (pintype "input"))
      (node (ref "E18") (pin "3") (pinfunction "CLK_3") (pintype "input"))
      (node (ref "E39") (pin "6") (pinfunction "O_6") (pintype "output"))
    )
    (net (code "121") (name "Net-(E17A-~{Q})") (class "Default")
      (node (ref "E17") (pin "6") (pinfunction "~{Q}_6") (pintype "output"))
      (node (ref "E26") (pin "7") (pinfunction "I0_7") (pintype "input"))
    )
    (net (code "122") (name "Net-(E17B-~{Q})") (class "Default")
      (node (ref "E17") (pin "8") (pinfunction "~{Q}_8") (pintype "output"))
      (node (ref "E26") (pin "1") (pinfunction "I0_1") (pintype "input"))
    )
    (net (code "123") (name "Net-(E18A-~{Q})") (class "Default")
      (node (ref "E18") (pin "6") (pinfunction "~{Q}_6") (pintype "output"))
      (node (ref "E27") (pin "7") (pinfunction "I0_7") (pintype "input"))
    )
    (net (code "124") (name "Net-(E18B-~{Q})") (class "Default")
      (node (ref "E18") (pin "8") (pinfunction "~{Q}_8") (pintype "output"))
      (node (ref "E27") (pin "1") (pinfunction "I0_1") (pintype "input"))
    )
    (net (code "125") (name "Net-(E19A-I0)") (class "Default")
      (node (ref "E19") (pin "1") (pinfunction "I0_1") (pintype "input"))
      (node (ref "E43") (pin "8") (pinfunction "~{Q}_8") (pintype "output"))
    )
    (net (code "126") (name "Net-(E19B-I0)") (class "Default")
      (node (ref "E19") (pin "7") (pinfunction "I0_7") (pintype "input"))
      (node (ref "E43") (pin "6") (pinfunction "~{Q}_6") (pintype "output"))
    )
    (net (code "127") (name "Net-(E20A-I0)") (class "Default")
      (node (ref "E20") (pin "1") (pinfunction "I0_1") (pintype "input"))
      (node (ref "E42") (pin "8") (pinfunction "~{Q}_8") (pintype "output"))
    )
    (net (code "128") (name "Net-(E20B-I0)") (class "Default")
      (node (ref "E20") (pin "7") (pinfunction "I0_7") (pintype "input"))
      (node (ref "E42") (pin "6") (pinfunction "~{Q}_6") (pintype "output"))
    )
    (net (code "129") (name "Net-(E21A-I0)") (class "Default")
      (node (ref "E21") (pin "1") (pinfunction "I0_1") (pintype "input"))
      (node (ref "E3") (pin "8") (pinfunction "O_8") (pintype "output"))
    )
    (net (code "130") (name "Net-(E22A-IN)") (class "Default")
      (node (ref "E22") (pin "1") (pinfunction "IN_1") (pintype "input"))
      (node (ref "E24") (pin "7") (pinfunction "Y2_7") (pintype "tri_state"))
      (node (ref "E28") (pin "1") (pinfunction "IN_1") (pintype "input"))
    )
    (net (code "131") (name "Net-(E22A-TAP1)") (class "Default")
      (node (ref "E22") (pin "7") (pinfunction "TAP1_7") (pintype "output"))
      (node (ref "E28") (pin "12") (pinfunction "TAP1_12") (pintype "output"))
    )
    (net (code "132") (name "Net-(E22A-TAP2)") (class "Default")
      (node (ref "E22") (pin "2") (pinfunction "TAP2_2") (pintype "output"))
      (node (ref "E28") (pin "4") (pinfunction "TAP2_4") (pintype "output"))
    )
    (net (code "133") (name "Net-(E22A-TAP3)") (class "Default")
      (node (ref "E22") (pin "6") (pinfunction "TAP3_6") (pintype "output"))
      (node (ref "E28") (pin "10") (pinfunction "TAP3_10") (pintype "output"))
      (node (ref "E31") (pin "12") (pinfunction "I0_12") (pintype "input"))
    )
    (net (code "134") (name "Net-(E22A-TAP4)") (class "Default")
      (node (ref "E22") (pin "3") (pinfunction "TAP4_3") (pintype "output"))
      (node (ref "E28") (pin "6") (pinfunction "TAP4_6") (pintype "output"))
    )
    (net (code "135") (name "Net-(E22A-TAP5)") (class "Default")
      (node (ref "E22") (pin "5") (pinfunction "TAP5_5") (pintype "output"))
      (node (ref "E28") (pin "8") (pinfunction "TAP5_8") (pintype "output"))
    )
    (net (code "136") (name "Net-(E24A-A2)") (class "Default")
      (node (ref "E24") (pin "4") (pinfunction "A2_4") (pintype "input"))
      (node (ref "E31") (pin "13") (pinfunction "I1_13") (pintype "input"))
      (node (ref "E31") (pin "8") (pinfunction "O_8") (pintype "output"))
    )
    (net (code "137") (name "Net-(E24A-A3)") (class "Default")
      (node (ref "E24") (pin "6") (pinfunction "A3_6") (pintype "input"))
      (node (ref "E29") (pin "2") (pinfunction "I1_2") (pintype "input"))
      (node (ref "E29") (pin "6") (pinfunction "O_6") (pintype "output"))
    )
    (net (code "138") (name "Net-(E24B-A2)") (class "Default")
      (node (ref "E24") (pin "13") (pinfunction "A2_13") (pintype "input"))
      (node (ref "E31") (pin "2") (pinfunction "I1_2") (pintype "input"))
      (node (ref "E31") (pin "6") (pinfunction "O_6") (pintype "output"))
    )
    (net (code "139") (name "Net-(E25A-I0)") (class "Default")
      (node (ref "E2") (pin "8") (pinfunction "~{Q}_8") (pintype "output"))
      (node (ref "E25") (pin "1") (pinfunction "I0_1") (pintype "input"))
    )
    (net (code "140") (name "Net-(E25B-I0)") (class "Default")
      (node (ref "E2") (pin "6") (pinfunction "~{Q}_6") (pintype "output"))
      (node (ref "E25") (pin "7") (pinfunction "I0_7") (pintype "input"))
    )
    (net (code "141") (name "Net-(E29A-O)") (class "Default")
      (node (ref "C5") (pin "1") (pinfunction "1_1") (pintype "passive"))
      (node (ref "E29") (pin "3") (pinfunction "O_3") (pintype "output"))
      (node (ref "R30") (pin "1") (pinfunction "1_1") (pintype "passive"))
    )
    (net (code "142") (name "Net-(E29B-I0)") (class "Default")
      (node (ref "C5") (pin "2") (pinfunction "2_2") (pintype "passive"))
      (node (ref "D5") (pin "C") (pinfunction "C_C") (pintype "passive"))
      (node (ref "E29") (pin "4") (pinfunction "I0_4") (pintype "input"))
      (node (ref "E29") (pin "5") (pinfunction "I1_5") (pintype "input"))
      (node (ref "R29") (pin "2") (pinfunction "2_2") (pintype "passive"))
    )
    (net (code "143") (name "Net-(E29C-I0)") (class "Default")
      (node (ref "E29") (pin "9") (pinfunction "I0_9") (pintype "input"))
      (node (ref "PAD31") (pin "1") (pinfunction "P_1") (pintype "passive"))
    )
    (net (code "144") (name "Net-(E29C-I1)") (class "Default")
      (node (ref "E29") (pin "10") (pinfunction "I1_10") (pintype "input"))
      (node (ref "PAD32") (pin "1") (pinfunction "P_1") (pintype "passive"))
    )
    (net (code "145") (name "Net-(E29C-O)") (class "Default")
      (node (ref "E29") (pin "8") (pinfunction "O_8") (pintype "output"))
      (node (ref "PAD33") (pin "1") (pinfunction "P_1") (pintype "passive"))
    )
    (net (code "146") (name "Net-(E29D-I0)") (class "Default")
      (node (ref "E29") (pin "12") (pinfunction "I0_12") (pintype "input"))
      (node (ref "PAD34") (pin "1") (pinfunction "P_1") (pintype "passive"))
    )
    (net (code "147") (name "Net-(E29D-I1)") (class "Default")
      (node (ref "E29") (pin "13") (pinfunction "I1_13") (pintype "input"))
      (node (ref "PAD35") (pin "1") (pinfunction "P_1") (pintype "passive"))
    )
    (net (code "148") (name "Net-(E29D-O)") (class "Default")
      (node (ref "E29") (pin "11") (pinfunction "O_11") (pintype "output"))
      (node (ref "PAD36") (pin "1") (pinfunction "P_1") (pintype "passive"))
    )
    (net (code "149") (name "Net-(E30G-IN)") (class "Default")
      (node (ref "E3") (pin "12") (pinfunction "O_12") (pintype "output"))
      (node (ref "E30") (pin "1") (pinfunction "IN_1") (pintype "input"))
      (node (ref "E35") (pin "1") (pinfunction "IN_1") (pintype "input"))
    )
    (net (code "150") (name "Net-(E30G-TAP1)") (class "Default")
      (node (ref "E30") (pin "12") (pinfunction "TAP1_12") (pintype "output"))
      (node (ref "E35") (pin "7") (pinfunction "TAP1_7") (pintype "output"))
    )
    (net (code "151") (name "Net-(E30G-TAP2)") (class "Default")
      (node (ref "E30") (pin "4") (pinfunction "TAP2_4") (pintype "output"))
      (node (ref "E35") (pin "2") (pinfunction "TAP2_2") (pintype "output"))
    )
    (net (code "152") (name "Net-(E30G-TAP3)") (class "Default")
      (node (ref "E30") (pin "10") (pinfunction "TAP3_10") (pintype "output"))
      (node (ref "E35") (pin "6") (pinfunction "TAP3_6") (pintype "output"))
    )
    (net (code "153") (name "Net-(E30G-TAP4)") (class "Default")
      (node (ref "E30") (pin "6") (pinfunction "TAP4_6") (pintype "output"))
      (node (ref "E31") (pin "1") (pinfunction "I0_1") (pintype "input"))
      (node (ref "E35") (pin "3") (pinfunction "TAP4_3") (pintype "output"))
    )
    (net (code "154") (name "Net-(E30G-TAP5)") (class "Default")
      (node (ref "E30") (pin "8") (pinfunction "TAP5_8") (pintype "output"))
      (node (ref "E35") (pin "5") (pinfunction "TAP5_5") (pintype "output"))
    )
    (net (code "155") (name "Net-(E31A-O)") (class "Default")
      (node (ref "C2") (pin "1") (pinfunction "1_1") (pintype "passive"))
      (node (ref "E31") (pin "3") (pinfunction "O_3") (pintype "output"))
      (node (ref "R22") (pin "1") (pinfunction "1_1") (pintype "passive"))
    )
    (net (code "156") (name "Net-(E31B-I0)") (class "Default")
      (node (ref "C2") (pin "2") (pinfunction "2_2") (pintype "passive"))
      (node (ref "D2") (pin "C") (pinfunction "C_C") (pintype "passive"))
      (node (ref "E31") (pin "4") (pinfunction "I0_4") (pintype "input"))
      (node (ref "E31") (pin "5") (pinfunction "I1_5") (pintype "input"))
      (node (ref "R21") (pin "2") (pinfunction "2_2") (pintype "passive"))
    )
    (net (code "157") (name "Net-(E31C-I0)") (class "Default")
      (node (ref "C4") (pin "2") (pinfunction "2_2") (pintype "passive"))
      (node (ref "D4") (pin "C") (pinfunction "C_C") (pintype "passive"))
      (node (ref "E31") (pin "10") (pinfunction "I1_10") (pintype "input"))
      (node (ref "E31") (pin "9") (pinfunction "I0_9") (pintype "input"))
      (node (ref "R27") (pin "2") (pinfunction "2_2") (pintype "passive"))
    )
    (net (code "158") (name "Net-(E31D-O)") (class "Default")
      (node (ref "C4") (pin "1") (pinfunction "1_1") (pintype "passive"))
      (node (ref "E31") (pin "11") (pinfunction "O_11") (pintype "output"))
      (node (ref "R28") (pin "1") (pinfunction "1_1") (pintype "passive"))
    )
    (net (code "159") (name "Net-(E32A-I0)") (class "Default")
      (node (ref "E32") (pin "1") (pinfunction "I0_1") (pintype "input"))
      (node (ref "E5") (pin "8") (pinfunction "~{Q}_8") (pintype "output"))
    )
    (net (code "160") (name "Net-(E32B-I0)") (class "Default")
      (node (ref "E32") (pin "7") (pinfunction "I0_7") (pintype "input"))
      (node (ref "E5") (pin "6") (pinfunction "~{Q}_6") (pintype "output"))
    )
    (net (code "161") (name "Net-(E38B-A1)") (class "Default")
      (node (ref "E38") (pin "11") (pinfunction "A1_11") (pintype "input"))
      (node (ref "PAD5") (pin "1") (pinfunction "P_1") (pintype "passive"))
    )
    (net (code "162") (name "Net-(E38B-A2)") (class "Default")
      (node (ref "E38") (pin "13") (pinfunction "A2_13") (pintype "input"))
      (node (ref "PAD6") (pin "1") (pinfunction "P_1") (pintype "passive"))
    )
    (net (code "163") (name "Net-(E38B-A3)") (class "Default")
      (node (ref "E38") (pin "15") (pinfunction "A3_15") (pintype "input"))
      (node (ref "PAD7") (pin "1") (pinfunction "P_1") (pintype "passive"))
    )
    (net (code "164") (name "Net-(E38B-A4)") (class "Default")
      (node (ref "E38") (pin "17") (pinfunction "A4_17") (pintype "input"))
      (node (ref "PAD8") (pin "1") (pinfunction "P_1") (pintype "passive"))
    )
    (net (code "165") (name "Net-(E38B-G)") (class "Default")
      (node (ref "E38") (pin "19") (pinfunction "G_19") (pintype "input"))
      (node (ref "PAD9") (pin "1") (pinfunction "P_1") (pintype "passive"))
    )
    (net (code "166") (name "Net-(E38B-Y1)") (class "Default")
      (node (ref "E38") (pin "9") (pinfunction "Y1_9") (pintype "tri_state"))
      (node (ref "PAD10") (pin "1") (pinfunction "P_1") (pintype "passive"))
    )
    (net (code "167") (name "Net-(E38B-Y2)") (class "Default")
      (node (ref "E38") (pin "7") (pinfunction "Y2_7") (pintype "tri_state"))
      (node (ref "PAD11") (pin "1") (pinfunction "P_1") (pintype "passive"))
    )
    (net (code "168") (name "Net-(E38B-Y3)") (class "Default")
      (node (ref "E38") (pin "5") (pinfunction "Y3_5") (pintype "tri_state"))
      (node (ref "PAD16") (pin "1") (pinfunction "P_1") (pintype "passive"))
    )
    (net (code "169") (name "Net-(E38B-Y4)") (class "Default")
      (node (ref "E38") (pin "3") (pinfunction "Y4_3") (pintype "tri_state"))
      (node (ref "PAD17") (pin "1") (pinfunction "P_1") (pintype "passive"))
    )
    (net (code "170") (name "Net-(E39C-O)") (class "Default")
      (node (ref "E39") (pin "8") (pinfunction "O_8") (pintype "output"))
      (node (ref "E42") (pin "11") (pinfunction "CLK_11") (pintype "input"))
      (node (ref "E42") (pin "3") (pinfunction "CLK_3") (pintype "input"))
      (node (ref "E43") (pin "11") (pinfunction "CLK_11") (pintype "input"))
      (node (ref "E43") (pin "3") (pinfunction "CLK_3") (pintype "input"))
    )
    (net (code "171") (name "Net-(E39D-I0)") (class "Default")
      (node (ref "E39") (pin "12") (pinfunction "I0_12") (pintype "input"))
      (node (ref "PAD42") (pin "1") (pinfunction "P_1") (pintype "passive"))
    )
    (net (code "172") (name "Net-(E39D-I1)") (class "Default")
      (node (ref "E39") (pin "13") (pinfunction "I1_13") (pintype "input"))
      (node (ref "PAD43") (pin "1") (pinfunction "P_1") (pintype "passive"))
    )
    (net (code "173") (name "Net-(E39D-O)") (class "Default")
      (node (ref "E39") (pin "11") (pinfunction "O_11") (pintype "output"))
      (node (ref "PAD44") (pin "1") (pinfunction "P_1") (pintype "passive"))
    )
    (net (code "174") (name "Net-(PAD18-P)") (class "Default")
      (node (ref "E44") (pin "1") (pinfunction "1_1") (pintype "passive"))
      (node (ref "PAD18") (pin "1") (pinfunction "P_1") (pintype "passive"))
    )
    (net (code "175") (name "Net-(PAD19-P)") (class "Default")
      (node (ref "E44") (pin "2") (pinfunction "2_2") (pintype "passive"))
      (node (ref "PAD19") (pin "1") (pinfunction "P_1") (pintype "passive"))
    )
    (net (code "176") (name "Net-(PAD20-P)") (class "Default")
      (node (ref "E44") (pin "3") (pinfunction "3_3") (pintype "passive"))
      (node (ref "PAD20") (pin "1") (pinfunction "P_1") (pintype "passive"))
    )
    (net (code "177") (name "Net-(PAD21-P)") (class "Default")
      (node (ref "E44") (pin "4") (pinfunction "4_4") (pintype "passive"))
      (node (ref "PAD21") (pin "1") (pinfunction "P_1") (pintype "passive"))
    )
    (net (code "178") (name "Net-(PAD22-P)") (class "Default")
      (node (ref "E44") (pin "5") (pinfunction "5_5") (pintype "passive"))
      (node (ref "PAD22") (pin "1") (pinfunction "P_1") (pintype "passive"))
    )
    (net (code "179") (name "Net-(PAD23-P)") (class "Default")
      (node (ref "E44") (pin "6") (pinfunction "6_6") (pintype "passive"))
      (node (ref "PAD23") (pin "1") (pinfunction "P_1") (pintype "passive"))
    )
    (net (code "180") (name "Net-(PAD24-P)") (class "Default")
      (node (ref "E44") (pin "7") (pinfunction "7_7") (pintype "passive"))
      (node (ref "PAD24") (pin "1") (pinfunction "P_1") (pintype "passive"))
    )
    (net (code "181") (name "Net-(PAD25-P)") (class "Default")
      (node (ref "E44") (pin "8") (pinfunction "8_8") (pintype "passive"))
      (node (ref "PAD25") (pin "1") (pinfunction "P_1") (pintype "passive"))
    )
    (net (code "182") (name "Net-(PAD26-P)") (class "Default")
      (node (ref "E44") (pin "16") (pinfunction "16_16") (pintype "passive"))
      (node (ref "PAD26") (pin "1") (pinfunction "P_1") (pintype "passive"))
    )
    (net (code "183") (name "Net-(PAD37-P)") (class "Default")
      (node (ref "E44") (pin "15") (pinfunction "15_15") (pintype "passive"))
      (node (ref "PAD37") (pin "1") (pinfunction "P_1") (pintype "passive"))
    )
    (net (code "184") (name "Net-(PAD38-P)") (class "Default")
      (node (ref "E44") (pin "14") (pinfunction "14_14") (pintype "passive"))
      (node (ref "PAD38") (pin "1") (pinfunction "P_1") (pintype "passive"))
    )
    (net (code "185") (name "Net-(PAD39-P)") (class "Default")
      (node (ref "E44") (pin "13") (pinfunction "13_13") (pintype "passive"))
      (node (ref "PAD39") (pin "1") (pinfunction "P_1") (pintype "passive"))
    )
    (net (code "186") (name "Net-(PAD40-P)") (class "Default")
      (node (ref "E44") (pin "12") (pinfunction "12_12") (pintype "passive"))
      (node (ref "PAD40") (pin "1") (pinfunction "P_1") (pintype "passive"))
    )
    (net (code "187") (name "Net-(PAD41-P)") (class "Default")
      (node (ref "E44") (pin "11") (pinfunction "11_11") (pintype "passive"))
      (node (ref "PAD41") (pin "1") (pinfunction "P_1") (pintype "passive"))
    )
    (net (code "188") (name "Net-(PAD45-P)") (class "Default")
      (node (ref "E44") (pin "10") (pinfunction "10_10") (pintype "passive"))
      (node (ref "PAD45") (pin "1") (pinfunction "P_1") (pintype "passive"))
    )
    (net (code "189") (name "Net-(PAD46-P)") (class "Default")
      (node (ref "E44") (pin "9") (pinfunction "9_9") (pintype "passive"))
      (node (ref "PAD46") (pin "1") (pinfunction "P_1") (pintype "passive"))
    )
    (net (code "190") (name "Net-(PAD47-P)") (class "Default")
      (node (ref "E13") (pin "1") (pinfunction "1_1") (pintype "passive"))
      (node (ref "PAD47") (pin "1") (pinfunction "P_1") (pintype "passive"))
    )
    (net (code "191") (name "Net-(PAD48-P)") (class "Default")
      (node (ref "E13") (pin "2") (pinfunction "2_2") (pintype "passive"))
      (node (ref "PAD48") (pin "1") (pinfunction "P_1") (pintype "passive"))
    )
    (net (code "192") (name "Net-(PAD49-P)") (class "Default")
      (node (ref "E13") (pin "3") (pinfunction "3_3") (pintype "passive"))
      (node (ref "PAD49") (pin "1") (pinfunction "P_1") (pintype "passive"))
    )
    (net (code "193") (name "Net-(PAD50-P)") (class "Default")
      (node (ref "E13") (pin "4") (pinfunction "4_4") (pintype "passive"))
      (node (ref "PAD50") (pin "1") (pinfunction "P_1") (pintype "passive"))
    )
    (net (code "194") (name "Net-(PAD51-P)") (class "Default")
      (node (ref "E13") (pin "5") (pinfunction "5_5") (pintype "passive"))
      (node (ref "PAD51") (pin "1") (pinfunction "P_1") (pintype "passive"))
    )
    (net (code "195") (name "Net-(PAD52-P)") (class "Default")
      (node (ref "E13") (pin "6") (pinfunction "6_6") (pintype "passive"))
      (node (ref "PAD52") (pin "1") (pinfunction "P_1") (pintype "passive"))
    )
    (net (code "196") (name "Net-(PAD53-P)") (class "Default")
      (node (ref "E13") (pin "7") (pinfunction "7_7") (pintype "passive"))
      (node (ref "PAD53") (pin "1") (pinfunction "P_1") (pintype "passive"))
    )
    (net (code "197") (name "Net-(PAD54-P)") (class "Default")
      (node (ref "E13") (pin "8") (pinfunction "8_8") (pintype "passive"))
      (node (ref "PAD54") (pin "1") (pinfunction "P_1") (pintype "passive"))
    )
    (net (code "198") (name "Net-(PAD55-P)") (class "Default")
      (node (ref "E13") (pin "16") (pinfunction "16_16") (pintype "passive"))
      (node (ref "PAD55") (pin "1") (pinfunction "P_1") (pintype "passive"))
    )
    (net (code "199") (name "Net-(PAD56-P)") (class "Default")
      (node (ref "E13") (pin "15") (pinfunction "15_15") (pintype "passive"))
      (node (ref "PAD56") (pin "1") (pinfunction "P_1") (pintype "passive"))
    )
    (net (code "200") (name "Net-(PAD57-P)") (class "Default")
      (node (ref "E13") (pin "14") (pinfunction "14_14") (pintype "passive"))
      (node (ref "PAD57") (pin "1") (pinfunction "P_1") (pintype "passive"))
    )
    (net (code "201") (name "Net-(PAD58-P)") (class "Default")
      (node (ref "E13") (pin "13") (pinfunction "13_13") (pintype "passive"))
      (node (ref "PAD58") (pin "1") (pinfunction "P_1") (pintype "passive"))
    )
    (net (code "202") (name "Net-(PAD59-P)") (class "Default")
      (node (ref "E13") (pin "12") (pinfunction "12_12") (pintype "passive"))
      (node (ref "PAD59") (pin "1") (pinfunction "P_1") (pintype "passive"))
    )
    (net (code "203") (name "Net-(PAD60-P)") (class "Default")
      (node (ref "E13") (pin "11") (pinfunction "11_11") (pintype "passive"))
      (node (ref "PAD60") (pin "1") (pinfunction "P_1") (pintype "passive"))
    )
    (net (code "204") (name "Net-(PAD61-P)") (class "Default")
      (node (ref "E13") (pin "10") (pinfunction "10_10") (pintype "passive"))
      (node (ref "PAD61") (pin "1") (pinfunction "P_1") (pintype "passive"))
    )
    (net (code "205") (name "Net-(PAD62-P)") (class "Default")
      (node (ref "E13") (pin "9") (pinfunction "9_9") (pintype "passive"))
      (node (ref "PAD62") (pin "1") (pinfunction "P_1") (pintype "passive"))
    )
    (net (code "206") (name "VCC") (class "Default")
      (node (ref "C10") (pin "1") (pinfunction "1_1") (pintype "passive"))
      (node (ref "C11") (pin "1") (pinfunction "1_1") (pintype "passive"))
      (node (ref "C12") (pin "1") (pinfunction "1_1") (pintype "passive"))
      (node (ref "C13") (pin "1") (pinfunction "1_1") (pintype "passive"))
      (node (ref "C14") (pin "1") (pinfunction "1_1") (pintype "passive"))
      (node (ref "C15") (pin "1") (pinfunction "1_1") (pintype "passive"))
      (node (ref "C16") (pin "1") (pinfunction "1_1") (pintype "passive"))
      (node (ref "C17") (pin "1") (pinfunction "1_1") (pintype "passive"))
      (node (ref "C18") (pin "1") (pinfunction "1_1") (pintype "passive"))
      (node (ref "C19") (pin "1") (pinfunction "1_1") (pintype "passive"))
      (node (ref "C20") (pin "1") (pinfunction "1_1") (pintype "passive"))
      (node (ref "C21") (pin "1") (pinfunction "1_1") (pintype "passive"))
      (node (ref "C22") (pin "1") (pinfunction "1_1") (pintype "passive"))
      (node (ref "C23") (pin "1") (pinfunction "1_1") (pintype "passive"))
      (node (ref "C24") (pin "1") (pinfunction "1_1") (pintype "passive"))
      (node (ref "C25") (pin "1") (pinfunction "1_1") (pintype "passive"))
      (node (ref "C26") (pin "1") (pinfunction "1_1") (pintype "passive"))
      (node (ref "C27") (pin "1") (pinfunction "1_1") (pintype "passive"))
      (node (ref "C28") (pin "1") (pinfunction "1_1") (pintype "passive"))
      (node (ref "C29") (pin "1") (pinfunction "1_1") (pintype "passive"))
      (node (ref "C30") (pin "1") (pinfunction "1_1") (pintype "passive"))
      (node (ref "C31") (pin "1") (pinfunction "1_1") (pintype "passive"))
      (node (ref "C32") (pin "1") (pinfunction "1_1") (pintype "passive"))
      (node (ref "C33") (pin "1") (pinfunction "1_1") (pintype "passive"))
      (node (ref "C34") (pin "1") (pinfunction "1_1") (pintype "passive"))
      (node (ref "C35") (pin "1") (pinfunction "1_1") (pintype "passive"))
      (node (ref "C36") (pin "1") (pinfunction "1_1") (pintype "passive"))
      (node (ref "C37") (pin "1") (pinfunction "1_1") (pintype "passive"))
      (node (ref "C38") (pin "1") (pinfunction "1_1") (pintype "passive"))
      (node (ref "C39") (pin "1") (pinfunction "1_1") (pintype "passive"))
      (node (ref "C40") (pin "1") (pinfunction "1_1") (pintype "passive"))
      (node (ref "C41") (pin "1") (pinfunction "1_1") (pintype "passive"))
      (node (ref "C42") (pin "1") (pinfunction "1_1") (pintype "passive"))
      (node (ref "C43") (pin "1") (pinfunction "1_1") (pintype "passive"))
      (node (ref "C44") (pin "1") (pinfunction "1_1") (pintype "passive"))
      (node (ref "C45") (pin "1") (pinfunction "1_1") (pintype "passive"))
      (node (ref "C46") (pin "1") (pinfunction "1_1") (pintype "passive"))
      (node (ref "C47") (pin "1") (pinfunction "1_1") (pintype "passive"))
      (node (ref "C48") (pin "1") (pinfunction "1_1") (pintype "passive"))
      (node (ref "C49") (pin "+") (pinfunction "+_+") (pintype "passive"))
      (node (ref "C50") (pin "+") (pinfunction "+_+") (pintype "passive"))
      (node (ref "C51") (pin "+") (pinfunction "+_+") (pintype "passive"))
      (node (ref "C52") (pin "+") (pinfunction "+_+") (pintype "passive"))
      (node (ref "C6") (pin "1") (pinfunction "1_1") (pintype "passive"))
      (node (ref "C7") (pin "1") (pinfunction "1_1") (pintype "passive"))
      (node (ref "C8") (pin "1") (pinfunction "1_1") (pintype "passive"))
      (node (ref "C9") (pin "1") (pinfunction "1_1") (pintype "passive"))
      (node (ref "E10") (pin "28") (pinfunction "VCC_28") (pintype "power_in"))
      (node (ref "E16") (pin "28") (pinfunction "VCC_28") (pintype "power_in"))
      (node (ref "E4") (pin "2") (pinfunction "VCC_2") (pintype "power_in"))
      (node (ref "R15") (pin "1") (pinfunction "1_1") (pintype "passive"))
      (node (ref "R17") (pin "1") (pinfunction "1_1") (pintype "passive"))
      (node (ref "R22") (pin "2") (pinfunction "2_2") (pintype "passive"))
      (node (ref "R28") (pin "2") (pinfunction "2_2") (pintype "passive"))
      (node (ref "R30") (pin "2") (pinfunction "2_2") (pintype "passive"))
      (node (ref "VCC") (pin "1") (pinfunction "P_1") (pintype "passive"))
    )
    (net (code "207") (name "unconnected-(E2A-Q-Pad5)") (class "Default")
      (node (ref "E2") (pin "5") (pinfunction "Q_5") (pintype "output"))
    )
    (net (code "208") (name "unconnected-(E2B-Q-Pad9)") (class "Default")
      (node (ref "E2") (pin "9") (pinfunction "Q_9") (pintype "output"))
    )
    (net (code "209") (name "unconnected-(E5A-Q-Pad5)") (class "Default")
      (node (ref "E5") (pin "5") (pinfunction "Q_5") (pintype "output"))
    )
    (net (code "210") (name "unconnected-(E5B-Q-Pad9)") (class "Default")
      (node (ref "E5") (pin "9") (pinfunction "Q_9") (pintype "output"))
    )
    (net (code "211") (name "unconnected-(E6A-Q-Pad5)") (class "Default")
      (node (ref "E6") (pin "5") (pinfunction "Q_5") (pintype "output"))
    )
    (net (code "212") (name "unconnected-(E6B-Q-Pad9)") (class "Default")
      (node (ref "E6") (pin "9") (pinfunction "Q_9") (pintype "output"))
    )
    (net (code "213") (name "unconnected-(E9A-~{Q}-Pad6)") (class "Default")
      (node (ref "E9") (pin "6") (pinfunction "~{Q}_6") (pintype "output"))
    )
    (net (code "214") (name "unconnected-(E9B-Q-Pad9)") (class "Default")
      (node (ref "E9") (pin "9") (pinfunction "Q_9") (pintype "output"))
    )
    (net (code "215") (name "unconnected-(E10-I{slash}O6-Pad18)") (class "Default")
      (node (ref "E10") (pin "18") (pinfunction "I/O6_18") (pintype "bidirectional"))
    )
    (net (code "216") (name "unconnected-(E10-I{slash}O7-Pad19)") (class "Default")
      (node (ref "E10") (pin "19") (pinfunction "I/O7_19") (pintype "bidirectional"))
    )
    (net (code "217") (name "unconnected-(E16-I{slash}O6-Pad18)") (class "Default")
      (node (ref "E16") (pin "18") (pinfunction "I/O6_18") (pintype "bidirectional"))
    )
    (net (code "218") (name "unconnected-(E16-I{slash}O7-Pad19)") (class "Default")
      (node (ref "E16") (pin "19") (pinfunction "I/O7_19") (pintype "bidirectional"))
    )
    (net (code "219") (name "unconnected-(E17A-Q-Pad5)") (class "Default")
      (node (ref "E17") (pin "5") (pinfunction "Q_5") (pintype "output"))
    )
    (net (code "220") (name "unconnected-(E17B-Q-Pad9)") (class "Default")
      (node (ref "E17") (pin "9") (pinfunction "Q_9") (pintype "output"))
    )
    (net (code "221") (name "unconnected-(E18A-Q-Pad5)") (class "Default")
      (node (ref "E18") (pin "5") (pinfunction "Q_5") (pintype "output"))
    )
    (net (code "222") (name "unconnected-(E18B-Q-Pad9)") (class "Default")
      (node (ref "E18") (pin "9") (pinfunction "Q_9") (pintype "output"))
    )
    (net (code "223") (name "unconnected-(E24A-Y1-Pad18)") (class "Default")
      (node (ref "E24") (pin "18") (pinfunction "Y1_18") (pintype "tri_state"))
    )
    (net (code "224") (name "unconnected-(E24A-Y4-Pad12)") (class "Default")
      (node (ref "E24") (pin "12") (pinfunction "Y4_12") (pintype "tri_state"))
    )
    (net (code "225") (name "unconnected-(E24B-Y1-Pad9)") (class "Default")
      (node (ref "E24") (pin "9") (pinfunction "Y1_9") (pintype "tri_state"))
    )
    (net (code "226") (name "unconnected-(E24B-Y3-Pad5)") (class "Default")
      (node (ref "E24") (pin "5") (pinfunction "Y3_5") (pintype "tri_state"))
    )
    (net (code "227") (name "unconnected-(E24B-Y4-Pad3)") (class "Default")
      (node (ref "E24") (pin "3") (pinfunction "Y4_3") (pintype "tri_state"))
    )
    (net (code "228") (name "unconnected-(E38A-Y4-Pad12)") (class "Default")
      (node (ref "E38") (pin "12") (pinfunction "Y4_12") (pintype "tri_state"))
    )
    (net (code "229") (name "unconnected-(E42A-Q-Pad5)") (class "Default")
      (node (ref "E42") (pin "5") (pinfunction "Q_5") (pintype "output"))
    )
    (net (code "230") (name "unconnected-(E42B-Q-Pad9)") (class "Default")
      (node (ref "E42") (pin "9") (pinfunction "Q_9") (pintype "output"))
    )
    (net (code "231") (name "unconnected-(E43A-Q-Pad5)") (class "Default")
      (node (ref "E43") (pin "5") (pinfunction "Q_5") (pintype "output"))
    )
    (net (code "232") (name "unconnected-(E43B-Q-Pad9)") (class "Default")
      (node (ref "E43") (pin "9") (pinfunction "Q_9") (pintype "output"))
    )
    (net (code "233") (name "unconnected-(H01/H20-Pad2)") (class "Default")
      (node (ref "H01/H20") (pin "2") (pinfunction "2_2") (pintype "passive"))
    )
    (net (code "234") (name "unconnected-(H01/H20-Pad4)") (class "Default")
      (node (ref "H01/H20") (pin "4") (pinfunction "4_4") (pintype "passive"))
    )
    (net (code "235") (name "unconnected-(H01/H20-Pad10)") (class "Default")
      (node (ref "H01/H20") (pin "10") (pinfunction "10_10") (pintype "passive"))
    )
    (net (code "236") (name "unconnected-(H01/H20-Pad14)") (class "Default")
      (node (ref "H01/H20") (pin "14") (pinfunction "14_14") (pintype "passive"))
    )
    (net (code "237") (name "unconnected-(H01/H20-Pad18)") (class "Default")
      (node (ref "H01/H20") (pin "18") (pinfunction "18_18") (pintype "passive"))
    )
    (net (code "238") (name "unconnected-(H01/H20-Pad22)") (class "Default")
      (node (ref "H01/H20") (pin "22") (pinfunction "22_22") (pintype "passive"))
    )
    (net (code "239") (name "unconnected-(H01/H20-Pad26)") (class "Default")
      (node (ref "H01/H20") (pin "26") (pinfunction "26_26") (pintype "passive"))
    )
    (net (code "240") (name "unconnected-(H01/H20-Pad34)") (class "Default")
      (node (ref "H01/H20") (pin "34") (pinfunction "34_34") (pintype "passive"))
    )
    (net (code "241") (name "unconnected-(H02/H21-Pad2)") (class "Default")
      (node (ref "H02/H21") (pin "2") (pinfunction "2_2") (pintype "passive"))
    )
    (net (code "242") (name "unconnected-(H02/H21-Pad4)") (class "Default")
      (node (ref "H02/H21") (pin "4") (pinfunction "4_4") (pintype "passive"))
    )
    (net (code "243") (name "unconnected-(H02/H21-Pad10)") (class "Default")
      (node (ref "H02/H21") (pin "10") (pinfunction "10_10") (pintype "passive"))
    )
    (net (code "244") (name "unconnected-(H02/H21-Pad14)") (class "Default")
      (node (ref "H02/H21") (pin "14") (pinfunction "14_14") (pintype "passive"))
    )
    (net (code "245") (name "unconnected-(H02/H21-Pad18)") (class "Default")
      (node (ref "H02/H21") (pin "18") (pinfunction "18_18") (pintype "passive"))
    )
    (net (code "246") (name "unconnected-(H02/H21-Pad22)") (class "Default")
      (node (ref "H02/H21") (pin "22") (pinfunction "22_22") (pintype "passive"))
    )
    (net (code "247") (name "unconnected-(H02/H21-Pad26)") (class "Default")
      (node (ref "H02/H21") (pin "26") (pinfunction "26_26") (pintype "passive"))
    )
    (net (code "248") (name "unconnected-(H02/H21-Pad34)") (class "Default")
      (node (ref "H02/H21") (pin "34") (pinfunction "34_34") (pintype "passive"))
    )
    (net (code "249") (name "unconnected-(H03/H22-Pad2)") (class "Default")
      (node (ref "H03/H22") (pin "2") (pinfunction "2_2") (pintype "passive"))
    )
    (net (code "250") (name "unconnected-(H03/H22-Pad4)") (class "Default")
      (node (ref "H03/H22") (pin "4") (pinfunction "4_4") (pintype "passive"))
    )
    (net (code "251") (name "unconnected-(H03/H22-Pad10)") (class "Default")
      (node (ref "H03/H22") (pin "10") (pinfunction "10_10") (pintype "passive"))
    )
    (net (code "252") (name "unconnected-(H03/H22-Pad14)") (class "Default")
      (node (ref "H03/H22") (pin "14") (pinfunction "14_14") (pintype "passive"))
    )
    (net (code "253") (name "unconnected-(H03/H22-Pad18)") (class "Default")
      (node (ref "H03/H22") (pin "18") (pinfunction "18_18") (pintype "passive"))
    )
    (net (code "254") (name "unconnected-(H03/H22-Pad22)") (class "Default")
      (node (ref "H03/H22") (pin "22") (pinfunction "22_22") (pintype "passive"))
    )
    (net (code "255") (name "unconnected-(H03/H22-Pad26)") (class "Default")
      (node (ref "H03/H22") (pin "26") (pinfunction "26_26") (pintype "passive"))
    )
    (net (code "256") (name "unconnected-(H03/H22-Pad34)") (class "Default")
      (node (ref "H03/H22") (pin "34") (pinfunction "34_34") (pintype "passive"))
    )
    (net (code "257") (name "unconnected-(H04/H23-Pad2)") (class "Default")
      (node (ref "H04/H23") (pin "2") (pinfunction "2_2") (pintype "passive"))
    )
    (net (code "258") (name "unconnected-(H04/H23-Pad4)") (class "Default")
      (node (ref "H04/H23") (pin "4") (pinfunction "4_4") (pintype "passive"))
    )
    (net (code "259") (name "unconnected-(H04/H23-Pad6)") (class "Default")
      (node (ref "H04/H23") (pin "6") (pinfunction "6_6") (pintype "passive"))
    )
    (net (code "260") (name "unconnected-(H04/H23-Pad10)") (class "Default")
      (node (ref "H04/H23") (pin "10") (pinfunction "10_10") (pintype "passive"))
    )
    (net (code "261") (name "unconnected-(H04/H23-Pad14)") (class "Default")
      (node (ref "H04/H23") (pin "14") (pinfunction "14_14") (pintype "passive"))
    )
    (net (code "262") (name "unconnected-(H04/H23-Pad18)") (class "Default")
      (node (ref "H04/H23") (pin "18") (pinfunction "18_18") (pintype "passive"))
    )
    (net (code "263") (name "unconnected-(H04/H23-Pad22)") (class "Default")
      (node (ref "H04/H23") (pin "22") (pinfunction "22_22") (pintype "passive"))
    )
    (net (code "264") (name "unconnected-(H04/H23-Pad26)") (class "Default")
      (node (ref "H04/H23") (pin "26") (pinfunction "26_26") (pintype "passive"))
    )
    (net (code "265") (name "unconnected-(H04/H23-Pad34)") (class "Default")
      (node (ref "H04/H23") (pin "34") (pinfunction "34_34") (pintype "passive"))
    )
    (net (code "266") (name "unconnected-(H05/H24-Pad2)") (class "Default")
      (node (ref "H05/H24") (pin "2") (pinfunction "2_2") (pintype "passive"))
    )
    (net (code "267") (name "unconnected-(H05/H24-Pad4)") (class "Default")
      (node (ref "H05/H24") (pin "4") (pinfunction "4_4") (pintype "passive"))
    )
    (net (code "268") (name "unconnected-(H05/H24-Pad10)") (class "Default")
      (node (ref "H05/H24") (pin "10") (pinfunction "10_10") (pintype "passive"))
    )
    (net (code "269") (name "unconnected-(H05/H24-Pad14)") (class "Default")
      (node (ref "H05/H24") (pin "14") (pinfunction "14_14") (pintype "passive"))
    )
    (net (code "270") (name "unconnected-(H05/H24-Pad18)") (class "Default")
      (node (ref "H05/H24") (pin "18") (pinfunction "18_18") (pintype "passive"))
    )
    (net (code "271") (name "unconnected-(H05/H24-Pad22)") (class "Default")
      (node (ref "H05/H24") (pin "22") (pinfunction "22_22") (pintype "passive"))
    )
    (net (code "272") (name "unconnected-(H05/H24-Pad26)") (class "Default")
      (node (ref "H05/H24") (pin "26") (pinfunction "26_26") (pintype "passive"))
    )
    (net (code "273") (name "unconnected-(H05/H24-Pad30)") (class "Default")
      (node (ref "H05/H24") (pin "30") (pinfunction "30_30") (pintype "passive"))
    )
    (net (code "274") (name "unconnected-(H05/H24-Pad34)") (class "Default")
      (node (ref "H05/H24") (pin "34") (pinfunction "34_34") (pintype "passive"))
    )
  )
)
